# Sheet.net
KiCad netlist of a schematic drawn in Altium Designer
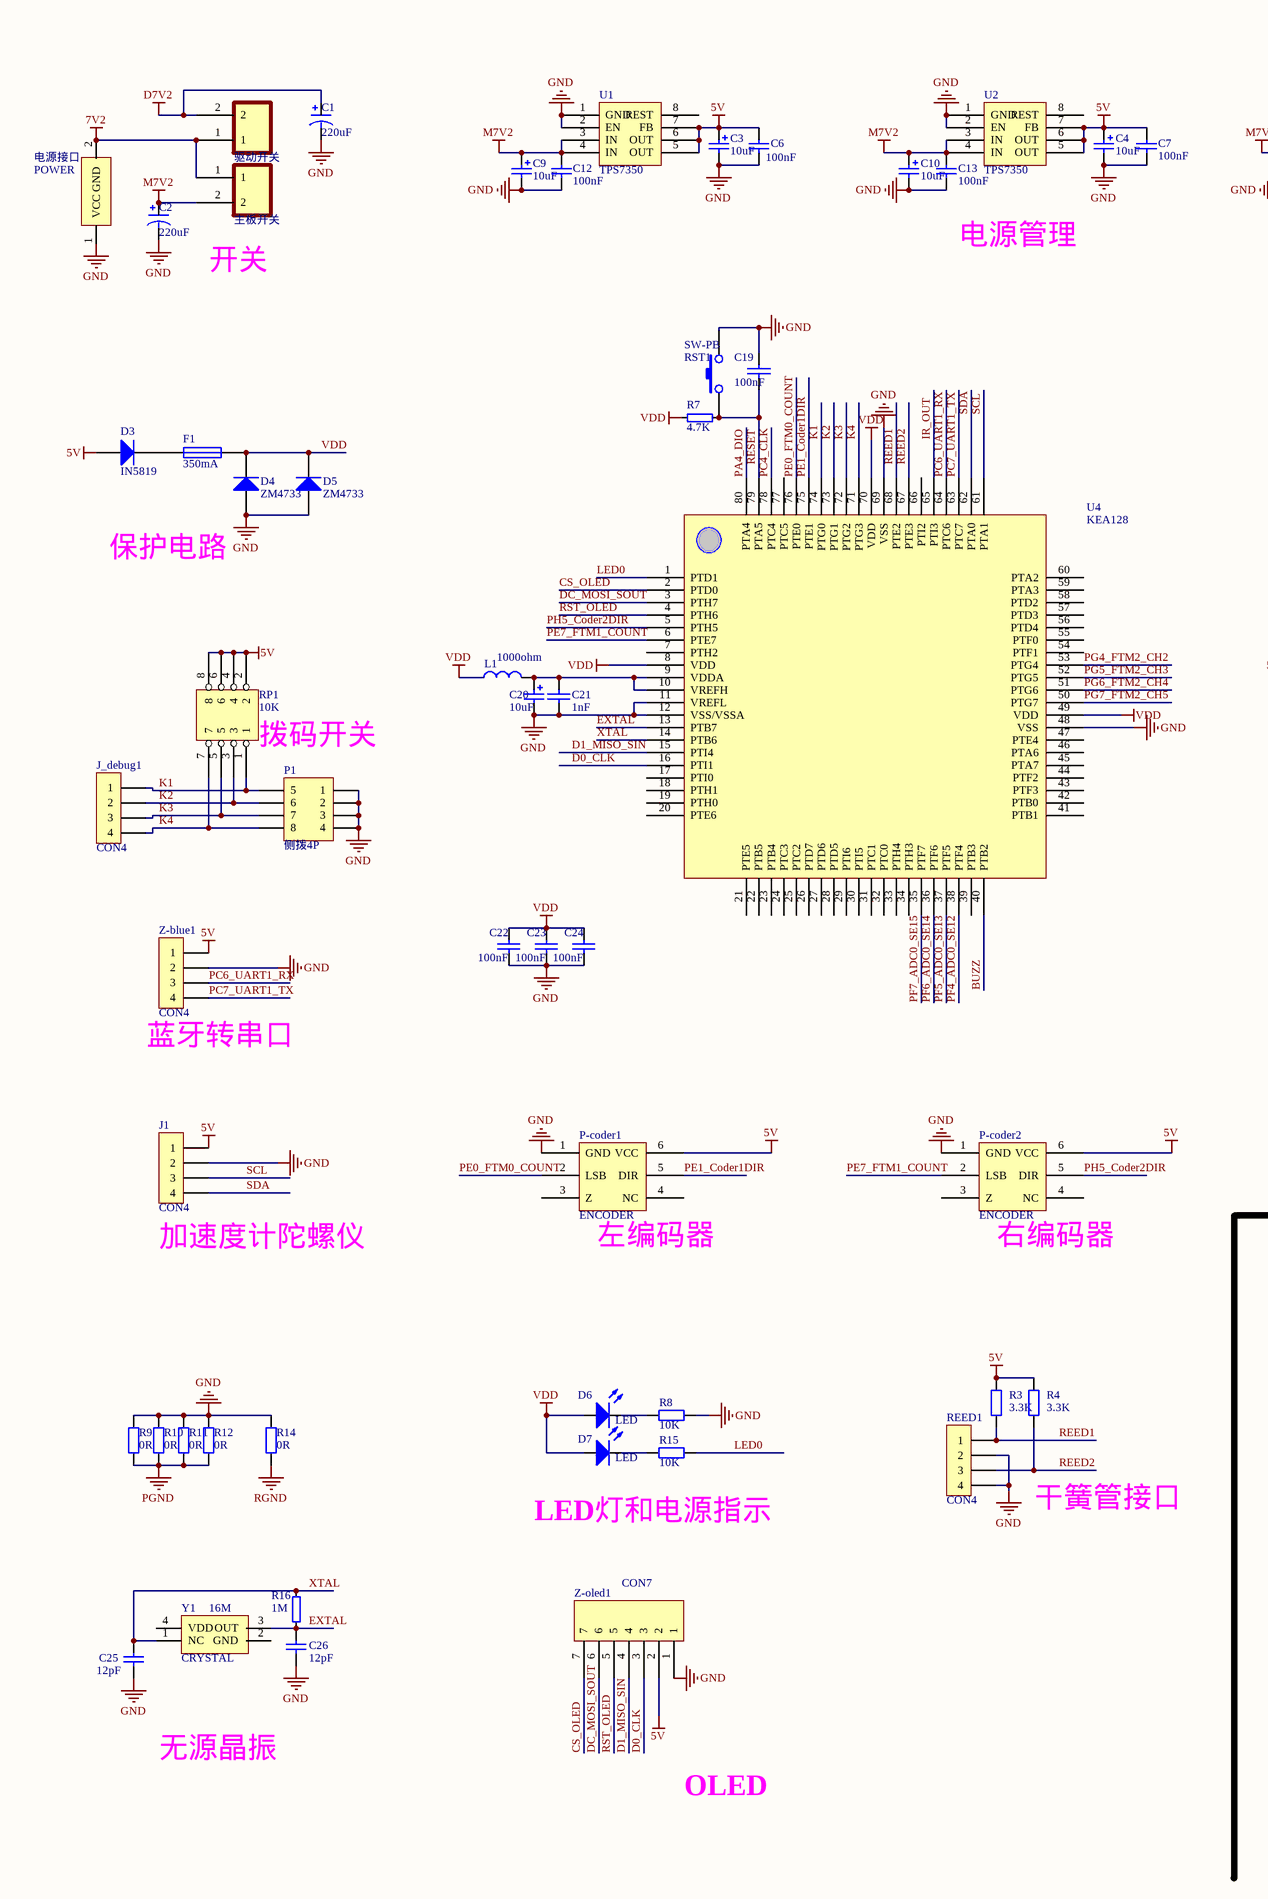
[diagram p0: 第十三届电磁Sheet.SchDoc, left]
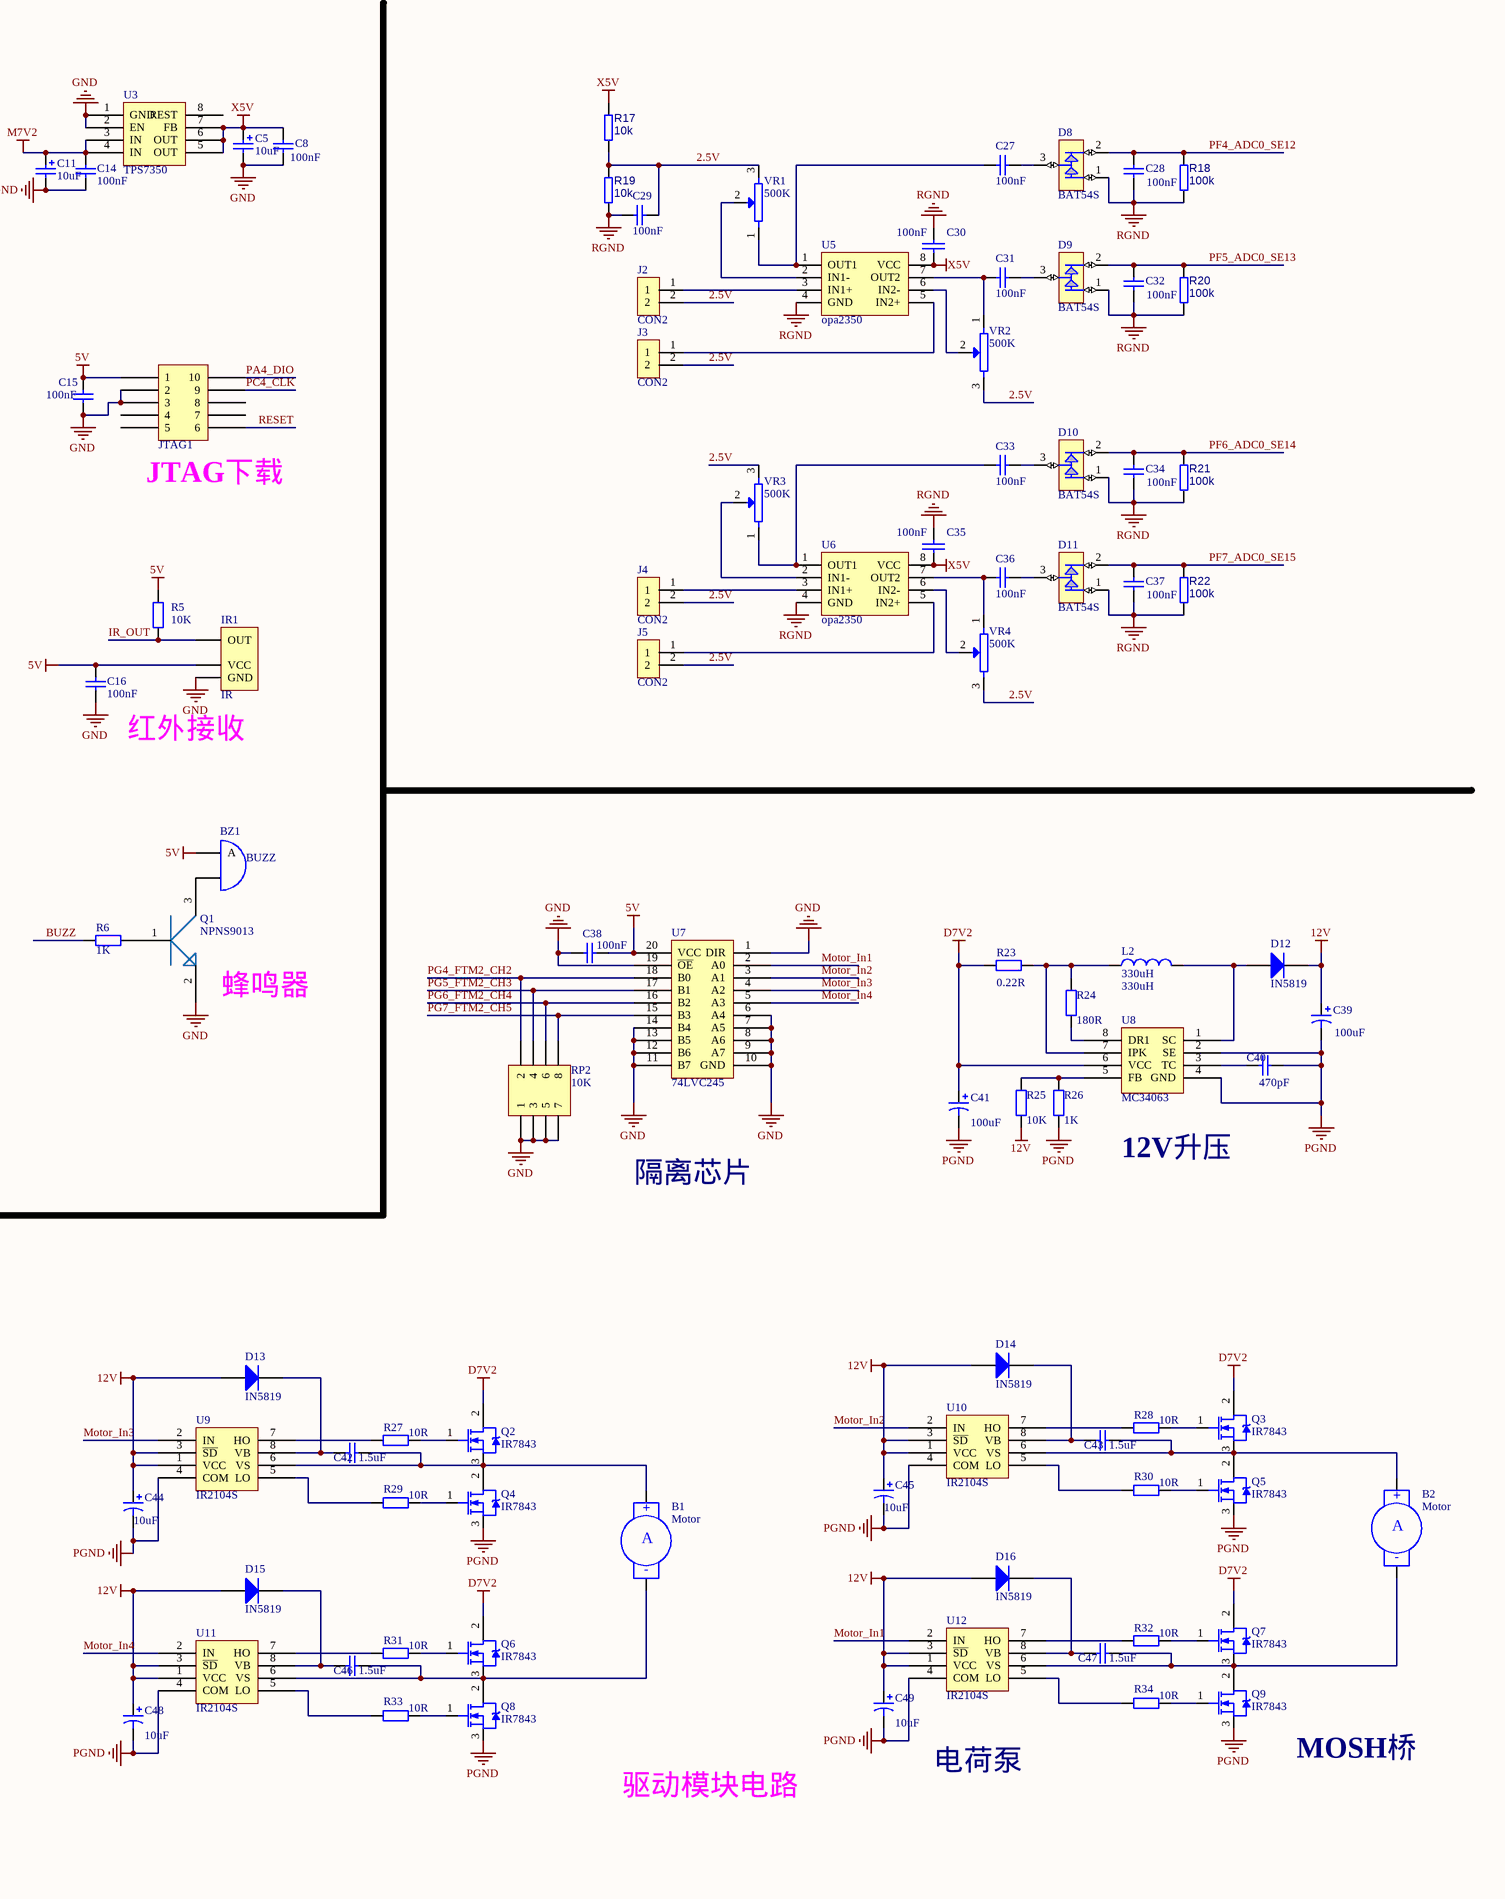
[diagram p1: 第十三届电磁Sheet.SchDoc, right]

(export (version "E")
  (design (tool "Eeschema 10.0.6"))
  (components
    (comp (ref "B1")
      (value "Motor")
      (footprint "KF301-2P")
      (description "Servo Motor")
      (libsource (lib "MOS motor driving module ") (part "Motor Servo"))
    )
    (comp (ref "B2")
      (value "Motor")
      (footprint "KF301-2P")
      (description "Servo Motor")
      (libsource (lib "MOS motor driving module ") (part "Motor Servo"))
    )
    (comp (ref "BZ1") (value "BUZZ") (footprint "BUZZ") (libsource (lib "原理图库") (part "BUZZ")))
    (comp (ref "C1")
      (value "220uF")
      (footprint "铝电解电容10*10.2")
      (description "电容带极性")
      (libsource (lib "原理图库") (part "CAP2"))
    )
    (comp (ref "C2")
      (value "220uF")
      (footprint "铝电解电容10*10.2")
      (description "电容带极性")
      (libsource (lib "原理图库") (part "CAP2"))
    )
    (comp (ref "C3") (value "10uF") (footprint "3216") (libsource (lib "飞思卡尔") (part "电容")))
    (comp (ref "C4") (value "10uF") (footprint "3216") (libsource (lib "飞思卡尔") (part "电容")))
    (comp (ref "C5") (value "10uF") (footprint "3216") (libsource (lib "飞思卡尔") (part "电容")))
    (comp (ref "C6")
      (value "100nF")
      (footprint "0603(1608)")
      (description "Capacitor")
      (libsource (lib "最小系统板K60P144-V4.0") (part "Cap"))
    )
    (comp (ref "C7")
      (value "100nF")
      (footprint "0603(1608)")
      (description "Capacitor")
      (libsource (lib "最小系统板K60P144-V4.0") (part "Cap"))
    )
    (comp (ref "C8")
      (value "100nF")
      (footprint "0603(1608)")
      (description "Capacitor")
      (libsource (lib "最小系统板K60P144-V4.0") (part "Cap"))
    )
    (comp (ref "C9") (value "10uF") (footprint "3216") (libsource (lib "飞思卡尔") (part "电容")))
    (comp (ref "C10") (value "10uF") (footprint "3216") (libsource (lib "飞思卡尔") (part "电容")))
    (comp (ref "C11") (value "10uF") (footprint "3216") (libsource (lib "飞思卡尔") (part "电容")))
    (comp (ref "C12")
      (value "100nF")
      (footprint "0603(1608)")
      (description "Capacitor")
      (libsource (lib "最小系统板K60P144-V4.0") (part "Cap"))
    )
    (comp (ref "C13")
      (value "100nF")
      (footprint "0603(1608)")
      (description "Capacitor")
      (libsource (lib "最小系统板K60P144-V4.0") (part "Cap"))
    )
    (comp (ref "C14")
      (value "100nF")
      (footprint "0603(1608)")
      (description "Capacitor")
      (libsource (lib "最小系统板K60P144-V4.0") (part "Cap"))
    )
    (comp (ref "C15")
      (value "100nF")
      (footprint "0603(1608)")
      (description "Capacitor")
      (libsource (lib "最小系统板K60P144-V4.0") (part "Cap"))
    )
    (comp (ref "C16")
      (value "100nF")
      (footprint "0603(1608)")
      (description "Capacitor")
      (fields (field (name "PUBLISHER") "Altium Limited"))
      (libsource (lib "国特原理图库") (part "Cap_1"))
    )
    (comp (ref "C19")
      (value "100nF")
      (footprint "0603(1608)")
      (description "Capacitor")
      (libsource (lib "K60芯片") (part "普通电容"))
    )
    (comp (ref "C20") (value "10uF") (footprint "3216") (libsource (lib "飞思卡尔") (part "电容")))
    (comp (ref "C21")
      (value "1nF")
      (footprint "0603(1608)")
      (description "Capacitor")
      (libsource (lib "K60芯片") (part "普通电容"))
    )
    (comp (ref "C22")
      (value "100nF")
      (footprint "0603(1608)")
      (description "Capacitor")
      (libsource (lib "K60芯片") (part "普通电容"))
    )
    (comp (ref "C23")
      (value "100nF")
      (footprint "0603(1608)")
      (description "Capacitor")
      (libsource (lib "K60芯片") (part "普通电容"))
    )
    (comp (ref "C24")
      (value "100nF")
      (footprint "0603(1608)")
      (description "Capacitor")
      (libsource (lib "K60芯片") (part "普通电容"))
    )
    (comp (ref "C25")
      (value "12pF")
      (footprint "0603(1608)")
      (description "Capacitor")
      (fields (field (name "PUBLISHER") "Altium Limited"))
      (libsource (lib "国特原理图库") (part "Cap_1"))
    )
    (comp (ref "C26")
      (value "12pF")
      (footprint "0603(1608)")
      (description "Capacitor")
      (fields (field (name "PUBLISHER") "Altium Limited"))
      (libsource (lib "国特原理图库") (part "Cap_1"))
    )
    (comp (ref "C27")
      (value "100nF")
      (footprint "0603(1608)")
      (description "Capacitor (Semiconductor SIM Model)")
      (fields (field (name "PUBLISHER") "Altium Limited"))
      (libsource (lib "电磁传感器V20") (part "Cap Semi"))
    )
    (comp (ref "C28")
      (value "100nF")
      (footprint "0603(1608)")
      (description "Capacitor (Semiconductor SIM Model)")
      (fields (field (name "PUBLISHER") "Altium Limited"))
      (libsource (lib "电磁传感器V20") (part "Cap Semi"))
    )
    (comp (ref "C29")
      (value "100nF")
      (footprint "0603(1608)")
      (description "Capacitor (Semiconductor SIM Model)")
      (fields (field (name "PUBLISHER") "Altium Limited"))
      (libsource (lib "电磁传感器V20") (part "Cap Semi"))
    )
    (comp (ref "C30")
      (value "100nF")
      (footprint "0603(1608)")
      (description "Capacitor")
      (libsource (lib "K60芯片") (part "普通电容"))
    )
    (comp (ref "C31")
      (value "100nF")
      (footprint "0603(1608)")
      (description "Capacitor (Semiconductor SIM Model)")
      (fields (field (name "PUBLISHER") "Altium Limited"))
      (libsource (lib "电磁传感器V20") (part "Cap Semi"))
    )
    (comp (ref "C32")
      (value "100nF")
      (footprint "0603(1608)")
      (description "Capacitor (Semiconductor SIM Model)")
      (fields (field (name "PUBLISHER") "Altium Limited"))
      (libsource (lib "电磁传感器V20") (part "Cap Semi"))
    )
    (comp (ref "C33")
      (value "100nF")
      (footprint "0603(1608)")
      (description "Capacitor (Semiconductor SIM Model)")
      (fields (field (name "PUBLISHER") "Altium Limited"))
      (libsource (lib "电磁传感器V20") (part "Cap Semi"))
    )
    (comp (ref "C34")
      (value "100nF")
      (footprint "0603(1608)")
      (description "Capacitor (Semiconductor SIM Model)")
      (fields (field (name "PUBLISHER") "Altium Limited"))
      (libsource (lib "电磁传感器V20") (part "Cap Semi"))
    )
    (comp (ref "C35")
      (value "100nF")
      (footprint "0603(1608)")
      (description "Capacitor")
      (libsource (lib "K60芯片") (part "普通电容"))
    )
    (comp (ref "C36")
      (value "100nF")
      (footprint "0603(1608)")
      (description "Capacitor (Semiconductor SIM Model)")
      (fields (field (name "PUBLISHER") "Altium Limited"))
      (libsource (lib "电磁传感器V20") (part "Cap Semi"))
    )
    (comp (ref "C37")
      (value "100nF")
      (footprint "0603(1608)")
      (description "Capacitor (Semiconductor SIM Model)")
      (fields (field (name "PUBLISHER") "Altium Limited"))
      (libsource (lib "电磁传感器V20") (part "Cap Semi"))
    )
    (comp (ref "C38")
      (value "100nF")
      (footprint "0603(1608)")
      (description "Capacitor")
      (fields (field (name "PUBLISHER") "Altium Limited"))
      (libsource (lib "Miscellaneous Devices") (part "Cap"))
    )
    (comp (ref "C39")
      (value "100uF")
      (footprint "TAN-D7343")
      (description "Polarized Capacitor (Radial)")
      (fields (field (name "PUBLISHER") "Altium Limited"))
      (libsource (lib "Miscellaneous Devices") (part "Cap Pol1"))
    )
    (comp (ref "C40")
      (value "470pF")
      (footprint "0603(1608)")
      (description "Capacitor")
      (fields (field (name "PUBLISHER") "Altium Limited"))
      (libsource (lib "Miscellaneous Devices") (part "Cap"))
    )
    (comp (ref "C41")
      (value "100uF")
      (footprint "TAN-D7343")
      (description "Polarized Capacitor (Radial)")
      (fields (field (name "PUBLISHER") "Altium Limited"))
      (libsource (lib "Miscellaneous Devices") (part "Cap Pol1"))
    )
    (comp (ref "C42")
      (value "1.5uF")
      (footprint "0603(1608)")
      (description "Capacitor")
      (fields (field (name "PUBLISHER") "Altium Limited"))
      (libsource (lib "Miscellaneous Devices") (part "Cap"))
    )
    (comp (ref "C43")
      (value "1.5uF")
      (footprint "0603(1608)")
      (description "Capacitor")
      (fields (field (name "PUBLISHER") "Altium Limited"))
      (libsource (lib "Miscellaneous Devices") (part "Cap"))
    )
    (comp (ref "C44")
      (value "10uF")
      (footprint "Tan-A3216")
      (description "Polarized Capacitor (Radial)")
      (fields (field (name "PUBLISHER") "Altium Limited"))
      (libsource (lib "Miscellaneous Devices") (part "Cap Pol1"))
    )
    (comp (ref "C45")
      (value "10uF")
      (footprint "Tan-A3216")
      (description "Polarized Capacitor (Radial)")
      (fields (field (name "PUBLISHER") "Altium Limited"))
      (libsource (lib "Miscellaneous Devices") (part "Cap Pol1"))
    )
    (comp (ref "C46")
      (value "1.5uF")
      (footprint "0603(1608)")
      (description "Capacitor")
      (fields (field (name "PUBLISHER") "Altium Limited"))
      (libsource (lib "Miscellaneous Devices") (part "Cap"))
    )
    (comp (ref "C47")
      (value "1.5uF")
      (footprint "0603(1608)")
      (description "Capacitor")
      (fields (field (name "PUBLISHER") "Altium Limited"))
      (libsource (lib "Miscellaneous Devices") (part "Cap"))
    )
    (comp (ref "C48")
      (value "10uF")
      (footprint "Tan-A3216")
      (description "Polarized Capacitor (Radial)")
      (fields (field (name "PUBLISHER") "Altium Limited"))
      (libsource (lib "Miscellaneous Devices") (part "Cap Pol1"))
    )
    (comp (ref "C49")
      (value "10uF")
      (footprint "Tan-A3216")
      (description "Polarized Capacitor (Radial)")
      (fields (field (name "PUBLISHER") "Altium Limited"))
      (libsource (lib "Miscellaneous Devices") (part "Cap Pol1"))
    )
    (comp (ref "D3")
      (value "IN5819")
      (footprint "LC-SOD-123")
      (description "Default Diode")
      (fields (field (name "PUBLISHER") "Altium Limited"))
      (libsource (lib "主板") (part "Diode"))
    )
    (comp (ref "D4")
      (value "ZM4733")
      (footprint "稳压管")
      (description "Default Diode")
      (fields (field (name "PUBLISHER") "Altium Limited"))
      (libsource (lib "主板") (part "Diode"))
    )
    (comp (ref "D5")
      (value "ZM4733")
      (footprint "稳压管")
      (description "Default Diode")
      (fields (field (name "PUBLISHER") "Altium Limited"))
      (libsource (lib "主板") (part "Diode"))
    )
    (comp (ref "D6")
      (value "LED")
      (footprint "0603LED")
      (description "Typical INFRARED GaAs LED")
      (libsource (lib "国特原理图库") (part "LED"))
    )
    (comp (ref "D7")
      (value "LED")
      (footprint "0603LED")
      (description "Typical INFRARED GaAs LED")
      (libsource (lib "国特原理图库") (part "LED"))
    )
    (comp (ref "D8")
      (value "BAT54S")
      (footprint "SOT23")
      (description "小信号肖特基二极管,峰值反向电压30 V,0.2A")
      (libsource (lib "电磁传感器V20") (part "BAT54S"))
    )
    (comp (ref "D9")
      (value "BAT54S")
      (footprint "SOT23")
      (description "小信号肖特基二极管,峰值反向电压30 V,0.2A")
      (libsource (lib "电磁传感器V20") (part "BAT54S"))
    )
    (comp (ref "D10")
      (value "BAT54S")
      (footprint "SOT23")
      (description "小信号肖特基二极管,峰值反向电压30 V,0.2A")
      (libsource (lib "电磁传感器V20") (part "BAT54S"))
    )
    (comp (ref "D11")
      (value "BAT54S")
      (footprint "SOT23")
      (description "小信号肖特基二极管,峰值反向电压30 V,0.2A")
      (libsource (lib "电磁传感器V20") (part "BAT54S"))
    )
    (comp (ref "D12")
      (value "IN5819")
      (footprint "LC-SOD-123")
      (description "Default Diode")
      (fields (field (name "PUBLISHER") "Altium Limited"))
      (libsource (lib "主板") (part "Diode"))
    )
    (comp (ref "D13")
      (value "IN5819")
      (footprint "LC-SOD-123")
      (description "Default Diode")
      (fields (field (name "PUBLISHER") "Altium Limited"))
      (libsource (lib "主板") (part "Diode"))
    )
    (comp (ref "D14")
      (value "IN5819")
      (footprint "LC-SOD-123")
      (description "Default Diode")
      (fields (field (name "PUBLISHER") "Altium Limited"))
      (libsource (lib "主板") (part "Diode"))
    )
    (comp (ref "D15")
      (value "IN5819")
      (footprint "LC-SOD-123")
      (description "Default Diode")
      (fields (field (name "PUBLISHER") "Altium Limited"))
      (libsource (lib "主板") (part "Diode"))
    )
    (comp (ref "D16")
      (value "IN5819")
      (footprint "LC-SOD-123")
      (description "Default Diode")
      (fields (field (name "PUBLISHER") "Altium Limited"))
      (libsource (lib "主板") (part "Diode"))
    )
    (comp (ref "F1")
      (value "350mA")
      (footprint "FUSE-1206")
      (description "Fuse")
      (fields (field (name "PUBLISHER") "Altium Limited"))
      (libsource (lib "最小系统板K60P144-V4.0") (part "Fuse 1"))
    )
    (comp (ref "IR1") (value "IR") (footprint "HS0038") (libsource (lib "原理图库") (part "IR_2")))
    (comp (ref "J1") (value "CON4") (footprint "CON4-1") (libsource (lib "原理图库") (part "CON4")))
    (comp (ref "J2") (value "CON2") (footprint "CON2") (libsource (lib "原理图库") (part "CON2")))
    (comp (ref "J3") (value "CON2") (footprint "CON2") (libsource (lib "原理图库") (part "CON2")))
    (comp (ref "J4") (value "CON2") (footprint "CON2") (libsource (lib "原理图库") (part "CON2")))
    (comp (ref "J5") (value "CON2") (footprint "CON2") (libsource (lib "原理图库") (part "CON2")))
    (comp (ref "JTAG1") (value "JTAG") (footprint "IDC5X2") (libsource (lib "国特原理图库") (part "JTAG")))
    (comp (ref "J_debug1") (value "CON4") (footprint "CON4-1") (libsource (lib "原理图库") (part "CON4")))
    (comp (ref "L1") (value "1000ohm") (footprint "0805 - duplicate") (libsource (lib "K60芯片") (part "L")))
    (comp (ref "L2")
      (value "330uH")
      (footprint "贴片电感7*7*4")
      (description "Inductor")
      (fields (field (name "ALTIUM_VALUE") "330uH") (field (name "PUBLISHER") "Altium Limited"))
      (libsource (lib "Miscellaneous Devices") (part "Inductor"))
    )
    (comp (ref "P-coder1") (value "ENCODER") (footprint "ENCODER") (libsource (lib "原理图库") (part "ENCODER")))
    (comp (ref "P-coder2") (value "ENCODER") (footprint "ENCODER") (libsource (lib "原理图库") (part "ENCODER")))
    (comp (ref "P1") (value "侧拨4P") (footprint "侧拨4P") (libsource (lib "原理图库") (part "侧拨4P")))
    (comp (ref "POWER")
      (value "电源接口")
      (footprint "KF301-2P")
      (description "2P")
      (libsource (lib "原理图库") (part "电源接口"))
    )
    (comp (ref "Q1")
      (value "NPNS9013")
      (footprint "LC-SOT-23(SOT-23-3)")
      (libsource (lib "原理图库") (part "S9013"))
    )
    (comp (ref "Q2")
      (value "IR7843")
      (footprint "LR7843")
      (description "N-Channel Power MOSFET")
      (fields (field (name "PUBLISHER") "Altium Limited"))
      (libsource (lib "MOS motor driving module ") (part "NMOS-2"))
    )
    (comp (ref "Q3")
      (value "IR7843")
      (footprint "LR7843")
      (description "N-Channel Power MOSFET")
      (fields (field (name "PUBLISHER") "Altium Limited"))
      (libsource (lib "MOS motor driving module ") (part "NMOS-2"))
    )
    (comp (ref "Q4")
      (value "IR7843")
      (footprint "LR7843 - no via")
      (description "N-Channel Power MOSFET")
      (fields (field (name "PUBLISHER") "Altium Limited"))
      (libsource (lib "MOS motor driving module ") (part "NMOS-2"))
    )
    (comp (ref "Q5")
      (value "IR7843")
      (footprint "LR7843 - no via")
      (description "N-Channel Power MOSFET")
      (fields (field (name "PUBLISHER") "Altium Limited"))
      (libsource (lib "MOS motor driving module ") (part "NMOS-2"))
    )
    (comp (ref "Q6")
      (value "IR7843")
      (footprint "LR7843")
      (description "N-Channel Power MOSFET")
      (fields (field (name "PUBLISHER") "Altium Limited"))
      (libsource (lib "MOS motor driving module ") (part "NMOS-2"))
    )
    (comp (ref "Q7")
      (value "IR7843")
      (footprint "LR7843")
      (description "N-Channel Power MOSFET")
      (fields (field (name "PUBLISHER") "Altium Limited"))
      (libsource (lib "MOS motor driving module ") (part "NMOS-2"))
    )
    (comp (ref "Q8")
      (value "IR7843")
      (footprint "LR7843 - no via")
      (description "N-Channel Power MOSFET")
      (fields (field (name "PUBLISHER") "Altium Limited"))
      (libsource (lib "MOS motor driving module ") (part "NMOS-2"))
    )
    (comp (ref "Q9")
      (value "IR7843")
      (footprint "LR7843 - no via")
      (description "N-Channel Power MOSFET")
      (fields (field (name "PUBLISHER") "Altium Limited"))
      (libsource (lib "MOS motor driving module ") (part "NMOS-2"))
    )
    (comp (ref "R3")
      (value "3.3K")
      (footprint "0603(1608)")
      (description "Resistor")
      (fields (field (name "PUBLISHER") "Altium Limited"))
      (libsource (lib "国特原理图库") (part "Res2_2"))
    )
    (comp (ref "R4")
      (value "3.3K")
      (footprint "0603(1608)")
      (description "Resistor")
      (fields (field (name "PUBLISHER") "Altium Limited"))
      (libsource (lib "国特原理图库") (part "Res2_2"))
    )
    (comp (ref "R5")
      (value "10K")
      (footprint "0603(1608)")
      (description "Resistor")
      (fields (field (name "PUBLISHER") "Altium Limited"))
      (libsource (lib "国特原理图库") (part "Res2_2"))
    )
    (comp (ref "R6")
      (value "1K")
      (footprint "0603(1608)")
      (description "Resistor")
      (fields (field (name "PUBLISHER") "Altium Limited"))
      (libsource (lib "") (part "Res2_2_1"))
    )
    (comp (ref "R7") (value "4.7K") (footprint "0603(1608)") (libsource (lib "K60芯片") (part "RES")))
    (comp (ref "R8")
      (value "10K")
      (footprint "0603(1608)")
      (description "Resistor")
      (fields (field (name "PUBLISHER") "Altium Limited"))
      (libsource (lib "国特原理图库") (part "Res2_1"))
    )
    (comp (ref "R9") (value "0R") (footprint "0805(2012)") (libsource (lib "飞思卡尔") (part "RES")))
    (comp (ref "R10") (value "0R") (footprint "0805(2012)") (libsource (lib "飞思卡尔") (part "RES")))
    (comp (ref "R11") (value "0R") (footprint "0805(2012)") (libsource (lib "飞思卡尔") (part "RES")))
    (comp (ref "R12") (value "0R") (footprint "0805(2012)") (libsource (lib "飞思卡尔") (part "RES")))
    (comp (ref "R14") (value "0R") (footprint "0805(2012)") (libsource (lib "飞思卡尔") (part "RES")))
    (comp (ref "R15")
      (value "10K")
      (footprint "0603(1608)")
      (description "Resistor")
      (fields (field (name "PUBLISHER") "Altium Limited"))
      (libsource (lib "国特原理图库") (part "Res2_1"))
    )
    (comp (ref "R16") (value "1M") (footprint "0603(1608)") (libsource (lib "K60芯片") (part "RES")))
    (comp (ref "R17")
      (value "10k")
      (footprint "0603(1608)")
      (description "单个电阻")
      (fields (field (name "PUBLISHER") "Altium Limited"))
      (libsource (lib "电磁传感器V20") (part "RES"))
    )
    (comp (ref "R18")
      (value "100k")
      (footprint "0603(1608)")
      (description "单个电阻")
      (fields (field (name "PUBLISHER") "Altium Limited"))
      (libsource (lib "电磁传感器V20") (part "RES"))
    )
    (comp (ref "R19")
      (value "10k")
      (footprint "0603(1608)")
      (description "单个电阻")
      (fields (field (name "PUBLISHER") "Altium Limited"))
      (libsource (lib "电磁传感器V20") (part "RES"))
    )
    (comp (ref "R20")
      (value "100k")
      (footprint "0603(1608)")
      (description "单个电阻")
      (fields (field (name "PUBLISHER") "Altium Limited"))
      (libsource (lib "电磁传感器V20") (part "RES"))
    )
    (comp (ref "R21")
      (value "100k")
      (footprint "0603(1608)")
      (description "单个电阻")
      (fields (field (name "PUBLISHER") "Altium Limited"))
      (libsource (lib "电磁传感器V20") (part "RES"))
    )
    (comp (ref "R22")
      (value "100k")
      (footprint "0603(1608)")
      (description "单个电阻")
      (fields (field (name "PUBLISHER") "Altium Limited"))
      (libsource (lib "电磁传感器V20") (part "RES"))
    )
    (comp (ref "R23")
      (value "0.22R")
      (footprint "0603(1608)")
      (description "Resistor")
      (fields (field (name "PUBLISHER") "Altium Limited"))
      (libsource (lib "Miscellaneous Devices") (part "Res2"))
    )
    (comp (ref "R24")
      (value "180R")
      (footprint "0603(1608)")
      (description "Resistor")
      (fields (field (name "PUBLISHER") "Altium Limited"))
      (libsource (lib "") (part "Res2_1"))
    )
    (comp (ref "R25")
      (value "10K")
      (footprint "0603(1608)")
      (description "Resistor")
      (fields (field (name "PUBLISHER") "Altium Limited"))
      (libsource (lib "") (part "Res2_1"))
    )
    (comp (ref "R26")
      (value "1K")
      (footprint "0603(1608)")
      (description "Resistor")
      (fields (field (name "PUBLISHER") "Altium Limited"))
      (libsource (lib "") (part "Res2_1"))
    )
    (comp (ref "R27")
      (value "10R")
      (footprint "0603(1608)")
      (description "Resistor")
      (fields (field (name "PUBLISHER") "Altium Limited"))
      (libsource (lib "MOS motor driving module ") (part "Res2"))
    )
    (comp (ref "R28")
      (value "10R")
      (footprint "0603(1608)")
      (description "Resistor")
      (fields (field (name "PUBLISHER") "Altium Limited"))
      (libsource (lib "MOS motor driving module ") (part "Res2"))
    )
    (comp (ref "R29")
      (value "10R")
      (footprint "0603(1608)")
      (description "Resistor")
      (fields (field (name "PUBLISHER") "Altium Limited"))
      (libsource (lib "MOS motor driving module ") (part "Res2"))
    )
    (comp (ref "R30")
      (value "10R")
      (footprint "0603(1608)")
      (description "Resistor")
      (fields (field (name "PUBLISHER") "Altium Limited"))
      (libsource (lib "MOS motor driving module ") (part "Res2"))
    )
    (comp (ref "R31")
      (value "10R")
      (footprint "0603(1608)")
      (description "Resistor")
      (fields (field (name "PUBLISHER") "Altium Limited"))
      (libsource (lib "MOS motor driving module ") (part "Res2"))
    )
    (comp (ref "R32")
      (value "10R")
      (footprint "0603(1608)")
      (description "Resistor")
      (fields (field (name "PUBLISHER") "Altium Limited"))
      (libsource (lib "MOS motor driving module ") (part "Res2"))
    )
    (comp (ref "R33")
      (value "10R")
      (footprint "0603(1608)")
      (description "Resistor")
      (fields (field (name "PUBLISHER") "Altium Limited"))
      (libsource (lib "MOS motor driving module ") (part "Res2"))
    )
    (comp (ref "R34")
      (value "10R")
      (footprint "0603(1608)")
      (description "Resistor")
      (fields (field (name "PUBLISHER") "Altium Limited"))
      (libsource (lib "MOS motor driving module ") (part "Res2"))
    )
    (comp (ref "REED1") (value "CON4") (footprint "CON4-1") (libsource (lib "主板") (part "CON4")))
    (comp (ref "RP1") (value "10K") (footprint "RA_8") (libsource (lib "原理图库") (part "HEADER4*2")))
    (comp (ref "RP2")
      (value "10K")
      (footprint "RA_8")
      (description "Header, 4-Pin, Dual row")
      (fields (field (name "PUBLISHER") "Altium Limited"))
      (libsource (lib "Miscellaneous Connectors") (part "Header 4X2"))
    )
    (comp (ref "RST1") (value "SW-PB") (footprint "SMT_BUTTON") (libsource (lib "K60芯片") (part "微动开关")))
    (comp (ref "U1") (value "TPS7350") (footprint "SOIC-8") (libsource (lib "飞思卡尔") (part "TPS")))
    (comp (ref "U2") (value "TPS7350") (footprint "SOIC-8") (libsource (lib "飞思卡尔") (part "TPS")))
    (comp (ref "U3") (value "TPS7350") (footprint "SOIC-8") (libsource (lib "飞思卡尔") (part "TPS")))
    (comp (ref "U4") (value "KEA128") (footprint "LQFP-80M") (libsource (lib "主板") (part "KEA128-80")))
    (comp (ref "U5")
      (value "opa2350")
      (footprint "SO8")
      (description "放大器")
      (libsource (lib "opa2350") (part "opa2350"))
    )
    (comp (ref "U6")
      (value "opa2350")
      (footprint "SO8")
      (description "放大器")
      (libsource (lib "opa2350") (part "opa2350"))
    )
    (comp (ref "U7")
      (value "74LVC245")
      (footprint "74LVC245 TSSOP")
      (libsource (lib "原理图库") (part "74LVC245"))
    )
    (comp (ref "U8") (value "MC34063") (footprint "MC34063") (libsource (lib "原理图库") (part "MC34063")))
    (comp (ref "U9")
      (value "IR2104S")
      (footprint "IR2104")
      (libsource (lib "MOS motor driving module ") (part "IR2104S"))
    )
    (comp (ref "U10")
      (value "IR2104S")
      (footprint "IR2104")
      (libsource (lib "MOS motor driving module ") (part "IR2104S"))
    )
    (comp (ref "U11")
      (value "IR2104S")
      (footprint "IR2104")
      (libsource (lib "MOS motor driving module ") (part "IR2104S"))
    )
    (comp (ref "U12")
      (value "IR2104S")
      (footprint "IR2104")
      (libsource (lib "MOS motor driving module ") (part "IR2104S"))
    )
    (comp (ref "VR1")
      (value "500K")
      (footprint "电位器")
      (description "3端可调电阻")
      (libsource (lib "电磁传感器V20") (part "VR"))
    )
    (comp (ref "VR2")
      (value "500K")
      (footprint "电位器")
      (description "3端可调电阻")
      (libsource (lib "电磁传感器V20") (part "VR"))
    )
    (comp (ref "VR3")
      (value "500K")
      (footprint "电位器")
      (description "3端可调电阻")
      (libsource (lib "电磁传感器V20") (part "VR"))
    )
    (comp (ref "VR4")
      (value "500K")
      (footprint "电位器")
      (description "3端可调电阻")
      (libsource (lib "电磁传感器V20") (part "VR"))
    )
    (comp (ref "Y1")
      (value "CRYSTAL")
      (footprint "LC-SMD-3225_4P")
      (fields (field (name "ALTIUM_UNNAMED_1") "16M"))
      (libsource (lib "原理图库") (part "CRYSTAL"))
    )
    (comp (ref "Z-blue1") (value "CON4") (footprint "Bluetooth") (libsource (lib "原理图库") (part "CON4")))
    (comp (ref "Z-oled1") (value "CON7") (footprint "CON7_OLED") (libsource (lib "原理图库") (part "CON7")))
    (comp (ref "主板开关1") (value "主板开关") (footprint "船型开关-small") (libsource (lib "国特原理图库") (part "船型开关")))
    (comp (ref "驱动开关1") (value "驱动开关") (footprint "船型开关-small") (libsource (lib "") (part "船型开关_1")))
  )
  (nets
    (net (code "1") (name "/2.5V") (class "Default")
      (node (ref "C29") (pin "1") (pinfunction "1_1") (pintype "passive"))
      (node (ref "J2") (pin "2") (pinfunction "2_2") (pintype "passive"))
      (node (ref "J3") (pin "2") (pinfunction "2_2") (pintype "passive"))
      (node (ref "J4") (pin "2") (pinfunction "2_2") (pintype "passive"))
      (node (ref "J5") (pin "2") (pinfunction "2_2") (pintype "passive"))
      (node (ref "R17") (pin "1") (pinfunction "1_1") (pintype "passive"))
      (node (ref "R19") (pin "2") (pinfunction "2_2") (pintype "passive"))
      (node (ref "VR1") (pin "3") (pinfunction "3_3") (pintype "passive"))
      (node (ref "VR2") (pin "3") (pinfunction "3_3") (pintype "passive"))
      (node (ref "VR3") (pin "3") (pinfunction "3_3") (pintype "passive"))
      (node (ref "VR4") (pin "3") (pinfunction "3_3") (pintype "passive"))
    )
    (net (code "2") (name "/BUZZ") (class "Default")
      (node (ref "R6") (pin "2") (pinfunction "2_2") (pintype "passive"))
      (node (ref "U4") (pin "40") (pinfunction "PTB2_40") (pintype "passive"))
    )
    (net (code "3") (name "/CS_OLED") (class "Default")
      (node (ref "U4") (pin "2") (pinfunction "PTD0_2") (pintype "passive"))
      (node (ref "Z-oled1") (pin "7") (pinfunction "7_7") (pintype "passive"))
    )
    (net (code "4") (name "/D0_CLK") (class "Default")
      (node (ref "U4") (pin "16") (pinfunction "PTI1_16") (pintype "passive"))
      (node (ref "Z-oled1") (pin "3") (pinfunction "3_3") (pintype "passive"))
    )
    (net (code "5") (name "/D1_MISO_SIN") (class "Default")
      (node (ref "U4") (pin "15") (pinfunction "PTI4_15") (pintype "passive"))
      (node (ref "Z-oled1") (pin "4") (pinfunction "4_4") (pintype "passive"))
    )
    (net (code "6") (name "/DC_MOSI_SOUT") (class "Default")
      (node (ref "U4") (pin "3") (pinfunction "PTH7_3") (pintype "passive"))
      (node (ref "Z-oled1") (pin "6") (pinfunction "6_6") (pintype "passive"))
    )
    (net (code "7") (name "/EXTAL") (class "Default")
      (node (ref "C26") (pin "2") (pinfunction "2_2") (pintype "passive"))
      (node (ref "R16") (pin "2") (pinfunction "2_2") (pintype "passive"))
      (node (ref "U4") (pin "13") (pinfunction "PTB7_13") (pintype "passive"))
      (node (ref "Y1") (pin "3") (pinfunction "OUT_3") (pintype "passive"))
    )
    (net (code "8") (name "/IR_OUT") (class "Default")
      (node (ref "IR1") (pin "3") (pinfunction "OUT_3") (pintype "passive"))
      (node (ref "R5") (pin "1") (pinfunction "1_1") (pintype "passive"))
      (node (ref "U4") (pin "65") (pinfunction "PTI3_65") (pintype "passive"))
    )
    (net (code "9") (name "/K1") (class "Default")
      (node (ref "J_debug1") (pin "1") (pinfunction "1_1") (pintype "passive"))
      (node (ref "P1") (pin "5") (pinfunction "5_5") (pintype "passive"))
      (node (ref "RP1") (pin "1") (pinfunction "1_1") (pintype "passive"))
      (node (ref "U4") (pin "74") (pinfunction "PTG0_74") (pintype "passive"))
    )
    (net (code "10") (name "/K2") (class "Default")
      (node (ref "J_debug1") (pin "2") (pinfunction "2_2") (pintype "passive"))
      (node (ref "P1") (pin "6") (pinfunction "6_6") (pintype "passive"))
      (node (ref "RP1") (pin "3") (pinfunction "3_3") (pintype "passive"))
      (node (ref "U4") (pin "73") (pinfunction "PTG1_73") (pintype "passive"))
    )
    (net (code "11") (name "/K3") (class "Default")
      (node (ref "J_debug1") (pin "3") (pinfunction "3_3") (pintype "passive"))
      (node (ref "P1") (pin "7") (pinfunction "7_7") (pintype "passive"))
      (node (ref "RP1") (pin "5") (pinfunction "5_5") (pintype "passive"))
      (node (ref "U4") (pin "72") (pinfunction "PTG2_72") (pintype "passive"))
    )
    (net (code "12") (name "/K4") (class "Default")
      (node (ref "J_debug1") (pin "4") (pinfunction "4_4") (pintype "passive"))
      (node (ref "P1") (pin "8") (pinfunction "8_8") (pintype "passive"))
      (node (ref "RP1") (pin "7") (pinfunction "7_7") (pintype "passive"))
      (node (ref "U4") (pin "71") (pinfunction "PTG3_71") (pintype "passive"))
    )
    (net (code "13") (name "/LED0") (class "Default")
      (node (ref "R15") (pin "2") (pinfunction "2_2") (pintype "passive"))
      (node (ref "U4") (pin "1") (pinfunction "PTD1_1") (pintype "passive"))
    )
    (net (code "14") (name "/Motor_In1") (class "Default")
      (node (ref "U12") (pin "2") (pinfunction "IN_2") (pintype "passive"))
      (node (ref "U7") (pin "2") (pinfunction "A0_2") (pintype "passive"))
    )
    (net (code "15") (name "/Motor_In2") (class "Default")
      (node (ref "U10") (pin "2") (pinfunction "IN_2") (pintype "passive"))
      (node (ref "U7") (pin "3") (pinfunction "A1_3") (pintype "passive"))
    )
    (net (code "16") (name "/Motor_In3") (class "Default")
      (node (ref "U7") (pin "4") (pinfunction "A2_4") (pintype "passive"))
      (node (ref "U9") (pin "2") (pinfunction "IN_2") (pintype "passive"))
    )
    (net (code "17") (name "/Motor_In4") (class "Default")
      (node (ref "U11") (pin "2") (pinfunction "IN_2") (pintype "passive"))
      (node (ref "U7") (pin "5") (pinfunction "A3_5") (pintype "passive"))
    )
    (net (code "18") (name "/PA4_DIO") (class "Default")
      (node (ref "JTAG1") (pin "10") (pinfunction "10_10") (pintype "passive"))
      (node (ref "U4") (pin "80") (pinfunction "PTA4_80") (pintype "passive"))
    )
    (net (code "19") (name "/PC4_CLK") (class "Default")
      (node (ref "JTAG1") (pin "9") (pinfunction "9_9") (pintype "passive"))
      (node (ref "U4") (pin "78") (pinfunction "PTC4_78") (pintype "passive"))
    )
    (net (code "20") (name "/PC6_UART1_RX") (class "Default")
      (node (ref "U4") (pin "64") (pinfunction "PTC6_64") (pintype "passive"))
      (node (ref "Z-blue1") (pin "3") (pinfunction "3_3") (pintype "passive"))
    )
    (net (code "21") (name "/PC7_UART1_TX") (class "Default")
      (node (ref "U4") (pin "63") (pinfunction "PTC7_63") (pintype "passive"))
      (node (ref "Z-blue1") (pin "4") (pinfunction "4_4") (pintype "passive"))
    )
    (net (code "22") (name "/PE0_FTM0_COUNT") (class "Default")
      (node (ref "P-coder1") (pin "2") (pinfunction "LSB_2") (pintype "passive"))
      (node (ref "U4") (pin "76") (pinfunction "PTE0_76") (pintype "passive"))
    )
    (net (code "23") (name "/PE1_Coder1DIR") (class "Default")
      (node (ref "P-coder1") (pin "5") (pinfunction "DIR_5") (pintype "passive"))
      (node (ref "U4") (pin "75") (pinfunction "PTE1_75") (pintype "passive"))
    )
    (net (code "24") (name "/PE7_FTM1_COUNT") (class "Default")
      (node (ref "P-coder2") (pin "2") (pinfunction "LSB_2") (pintype "passive"))
      (node (ref "U4") (pin "6") (pinfunction "PTE7_6") (pintype "passive"))
    )
    (net (code "25") (name "/PF4_ADC0_SE12") (class "Default")
      (node (ref "C28") (pin "2") (pinfunction "2_2") (pintype "passive"))
      (node (ref "D8") (pin "2") (pintype "bidirectional"))
      (node (ref "R18") (pin "2") (pinfunction "2_2") (pintype "passive"))
      (node (ref "U4") (pin "38") (pinfunction "PTF4_38") (pintype "passive"))
    )
    (net (code "26") (name "/PF5_ADC0_SE13") (class "Default")
      (node (ref "C32") (pin "2") (pinfunction "2_2") (pintype "passive"))
      (node (ref "D9") (pin "2") (pintype "bidirectional"))
      (node (ref "R20") (pin "2") (pinfunction "2_2") (pintype "passive"))
      (node (ref "U4") (pin "37") (pinfunction "PTF5_37") (pintype "passive"))
    )
    (net (code "27") (name "/PF6_ADC0_SE14") (class "Default")
      (node (ref "C34") (pin "2") (pinfunction "2_2") (pintype "passive"))
      (node (ref "D10") (pin "2") (pintype "bidirectional"))
      (node (ref "R21") (pin "2") (pinfunction "2_2") (pintype "passive"))
      (node (ref "U4") (pin "36") (pinfunction "PTF6_36") (pintype "passive"))
    )
    (net (code "28") (name "/PF7_ADC0_SE15") (class "Default")
      (node (ref "C37") (pin "2") (pinfunction "2_2") (pintype "passive"))
      (node (ref "D11") (pin "2") (pintype "bidirectional"))
      (node (ref "R22") (pin "2") (pinfunction "2_2") (pintype "passive"))
      (node (ref "U4") (pin "35") (pinfunction "PTF7_35") (pintype "passive"))
    )
    (net (code "29") (name "/PG4_FTM2_CH2") (class "Default")
      (node (ref "RP2") (pin "2") (pinfunction "2_2") (pintype "passive"))
      (node (ref "U4") (pin "53") (pinfunction "PTG4_53") (pintype "passive"))
      (node (ref "U7") (pin "18") (pinfunction "B0_18") (pintype "passive"))
    )
    (net (code "30") (name "/PG5_FTM2_CH3") (class "Default")
      (node (ref "RP2") (pin "4") (pinfunction "4_4") (pintype "passive"))
      (node (ref "U4") (pin "52") (pinfunction "PTG5_52") (pintype "passive"))
      (node (ref "U7") (pin "17") (pinfunction "B1_17") (pintype "passive"))
    )
    (net (code "31") (name "/PG6_FTM2_CH4") (class "Default")
      (node (ref "RP2") (pin "6") (pinfunction "6_6") (pintype "passive"))
      (node (ref "U4") (pin "51") (pinfunction "PTG6_51") (pintype "passive"))
      (node (ref "U7") (pin "16") (pinfunction "B2_16") (pintype "passive"))
    )
    (net (code "32") (name "/PG7_FTM2_CH5") (class "Default")
      (node (ref "RP2") (pin "8") (pinfunction "8_8") (pintype "passive"))
      (node (ref "U4") (pin "50") (pinfunction "PTG7_50") (pintype "passive"))
      (node (ref "U7") (pin "15") (pinfunction "B3_15") (pintype "passive"))
    )
    (net (code "33") (name "/PH5_Coder2DIR") (class "Default")
      (node (ref "P-coder2") (pin "5") (pinfunction "DIR_5") (pintype "passive"))
      (node (ref "U4") (pin "5") (pinfunction "PTH5_5") (pintype "passive"))
    )
    (net (code "34") (name "/REED1") (class "Default")
      (node (ref "R3") (pin "1") (pinfunction "1_1") (pintype "passive"))
      (node (ref "REED1") (pin "1") (pinfunction "1_1") (pintype "passive"))
      (node (ref "U4") (pin "68") (pinfunction "PTE2_68") (pintype "passive"))
    )
    (net (code "35") (name "/REED2") (class "Default")
      (node (ref "R4") (pin "1") (pinfunction "1_1") (pintype "passive"))
      (node (ref "REED1") (pin "3") (pinfunction "3_3") (pintype "passive"))
      (node (ref "U4") (pin "67") (pinfunction "PTE3_67") (pintype "passive"))
    )
    (net (code "36") (name "/RESET") (class "Default")
      (node (ref "C19") (pin "1") (pinfunction "1_1") (pintype "passive"))
      (node (ref "JTAG1") (pin "6") (pinfunction "6_6") (pintype "passive"))
      (node (ref "R7") (pin "2") (pinfunction "2_2") (pintype "passive"))
      (node (ref "RST1") (pin "1") (pinfunction "1_1") (pintype "passive"))
      (node (ref "U4") (pin "79") (pinfunction "PTA5_79") (pintype "passive"))
    )
    (net (code "37") (name "/RST_OLED") (class "Default")
      (node (ref "U4") (pin "4") (pinfunction "PTH6_4") (pintype "passive"))
      (node (ref "Z-oled1") (pin "5") (pinfunction "5_5") (pintype "passive"))
    )
    (net (code "38") (name "/SCL") (class "Default")
      (node (ref "J1") (pin "3") (pinfunction "3_3") (pintype "passive"))
      (node (ref "U4") (pin "61") (pinfunction "PTA1_61") (pintype "passive"))
    )
    (net (code "39") (name "/SDA") (class "Default")
      (node (ref "J1") (pin "4") (pinfunction "4_4") (pintype "passive"))
      (node (ref "U4") (pin "62") (pinfunction "PTA0_62") (pintype "passive"))
    )
    (net (code "40") (name "/XTAL") (class "Default")
      (node (ref "C25") (pin "2") (pinfunction "2_2") (pintype "passive"))
      (node (ref "R16") (pin "1") (pinfunction "1_1") (pintype "passive"))
      (node (ref "U4") (pin "14") (pinfunction "PTB6_14") (pintype "passive"))
      (node (ref "Y1") (pin "1") (pinfunction "NC_1") (pintype "passive"))
    )
    (net (code "41") (name "5V") (class "Default")
      (node (ref "BZ1") (pin "1") (pinfunction "A_1") (pintype "passive"))
      (node (ref "C15") (pin "2") (pinfunction "2_2") (pintype "passive"))
      (node (ref "C16") (pin "2") (pinfunction "2_2") (pintype "passive"))
      (node (ref "C3") (pin "1") (pinfunction "1_1") (pintype "passive"))
      (node (ref "C38") (pin "2") (pinfunction "2_2") (pintype "passive"))
      (node (ref "C4") (pin "1") (pinfunction "1_1") (pintype "passive"))
      (node (ref "C6") (pin "2") (pinfunction "2_2") (pintype "passive"))
      (node (ref "C7") (pin "2") (pinfunction "2_2") (pintype "passive"))
      (node (ref "D3") (pin "1") (pinfunction "A_1") (pintype "passive"))
      (node (ref "IR1") (pin "2") (pinfunction "VCC_2") (pintype "passive"))
      (node (ref "J1") (pin "1") (pinfunction "1_1") (pintype "passive"))
      (node (ref "JTAG1") (pin "1") (pinfunction "1_1") (pintype "passive"))
      (node (ref "P-coder1") (pin "6") (pinfunction "VCC_6") (pintype "passive"))
      (node (ref "P-coder2") (pin "6") (pinfunction "VCC_6") (pintype "passive"))
      (node (ref "R3") (pin "2") (pinfunction "2_2") (pintype "passive"))
      (node (ref "R4") (pin "2") (pinfunction "2_2") (pintype "passive"))
      (node (ref "R5") (pin "2") (pinfunction "2_2") (pintype "passive"))
      (node (ref "RP1") (pin "2") (pinfunction "2_2") (pintype "passive"))
      (node (ref "RP1") (pin "4") (pinfunction "4_4") (pintype "passive"))
      (node (ref "RP1") (pin "6") (pinfunction "6_6") (pintype "passive"))
      (node (ref "RP1") (pin "8") (pinfunction "8_8") (pintype "passive"))
      (node (ref "U1") (pin "5") (pinfunction "OUT_5") (pintype "passive"))
      (node (ref "U1") (pin "6") (pinfunction "OUT_6") (pintype "passive"))
      (node (ref "U1") (pin "7") (pinfunction "FB_7") (pintype "passive"))
      (node (ref "U2") (pin "5") (pinfunction "OUT_5") (pintype "passive"))
      (node (ref "U2") (pin "6") (pinfunction "OUT_6") (pintype "passive"))
      (node (ref "U2") (pin "7") (pinfunction "FB_7") (pintype "passive"))
      (node (ref "U7") (pin "20") (pinfunction "VCC_20") (pintype "passive"))
      (node (ref "Z-blue1") (pin "1") (pinfunction "1_1") (pintype "passive"))
      (node (ref "Z-oled1") (pin "2") (pinfunction "2_2") (pintype "passive"))
    )
    (net (code "42") (name "7V2") (class "Default")
      (node (ref "POWER") (pin "2") (pinfunction "GND_2") (pintype "passive"))
      (node (ref "主板开关1") (pin "1") (pinfunction "1_1") (pintype "passive"))
      (node (ref "驱动开关1") (pin "1") (pinfunction "1_1") (pintype "passive"))
    )
    (net (code "43") (name "12V") (class "Default")
      (node (ref "C39") (pin "1") (pinfunction "1_1") (pintype "passive"))
      (node (ref "C44") (pin "1") (pinfunction "1_1") (pintype "passive"))
      (node (ref "C45") (pin "1") (pinfunction "1_1") (pintype "passive"))
      (node (ref "C48") (pin "1") (pinfunction "1_1") (pintype "passive"))
      (node (ref "C49") (pin "1") (pinfunction "1_1") (pintype "passive"))
      (node (ref "D12") (pin "2") (pinfunction "K_2") (pintype "passive"))
      (node (ref "D13") (pin "1") (pinfunction "A_1") (pintype "passive"))
      (node (ref "D14") (pin "1") (pinfunction "A_1") (pintype "passive"))
      (node (ref "D15") (pin "1") (pinfunction "A_1") (pintype "passive"))
      (node (ref "D16") (pin "1") (pinfunction "A_1") (pintype "passive"))
      (node (ref "R25") (pin "1") (pinfunction "1_1") (pintype "passive"))
      (node (ref "U10") (pin "1") (pinfunction "VCC_1") (pintype "passive"))
      (node (ref "U10") (pin "3") (pinfunction "~{SD}_3") (pintype "passive"))
      (node (ref "U11") (pin "1") (pinfunction "VCC_1") (pintype "passive"))
      (node (ref "U11") (pin "3") (pinfunction "~{SD}_3") (pintype "passive"))
      (node (ref "U12") (pin "1") (pinfunction "VCC_1") (pintype "passive"))
      (node (ref "U12") (pin "3") (pinfunction "~{SD}_3") (pintype "passive"))
      (node (ref "U9") (pin "1") (pinfunction "VCC_1") (pintype "passive"))
      (node (ref "U9") (pin "3") (pinfunction "~{SD}_3") (pintype "passive"))
    )
    (net (code "44") (name "D7V2") (class "Default")
      (node (ref "C1") (pin "1") (pinfunction "1_1") (pintype "passive"))
      (node (ref "C41") (pin "1") (pinfunction "1_1") (pintype "passive"))
      (node (ref "Q2") (pin "2") (pinfunction "D_2") (pintype "passive"))
      (node (ref "Q3") (pin "2") (pinfunction "D_2") (pintype "passive"))
      (node (ref "Q6") (pin "2") (pinfunction "D_2") (pintype "passive"))
      (node (ref "Q7") (pin "2") (pinfunction "D_2") (pintype "passive"))
      (node (ref "R23") (pin "2") (pinfunction "2_2") (pintype "passive"))
      (node (ref "U8") (pin "6") (pinfunction "VCC_6") (pintype "passive"))
      (node (ref "驱动开关1") (pin "2") (pinfunction "2_2") (pintype "passive"))
    )
    (net (code "45") (name "GND") (class "Default")
      (node (ref "C1") (pin "2") (pinfunction "2_2") (pintype "passive"))
      (node (ref "C10") (pin "2") (pinfunction "2_2") (pintype "passive"))
      (node (ref "C11") (pin "2") (pinfunction "2_2") (pintype "passive"))
      (node (ref "C12") (pin "2") (pinfunction "2_2") (pintype "passive"))
      (node (ref "C13") (pin "1") (pinfunction "1_1") (pintype "passive"))
      (node (ref "C14") (pin "2") (pinfunction "2_2") (pintype "passive"))
      (node (ref "C15") (pin "1") (pinfunction "1_1") (pintype "passive"))
      (node (ref "C16") (pin "1") (pinfunction "1_1") (pintype "passive"))
      (node (ref "C19") (pin "2") (pinfunction "2_2") (pintype "passive"))
      (node (ref "C2") (pin "2") (pinfunction "2_2") (pintype "passive"))
      (node (ref "C20") (pin "2") (pinfunction "2_2") (pintype "passive"))
      (node (ref "C21") (pin "1") (pinfunction "1_1") (pintype "passive"))
      (node (ref "C22") (pin "1") (pinfunction "1_1") (pintype "passive"))
      (node (ref "C23") (pin "1") (pinfunction "1_1") (pintype "passive"))
      (node (ref "C24") (pin "1") (pinfunction "1_1") (pintype "passive"))
      (node (ref "C25") (pin "1") (pinfunction "1_1") (pintype "passive"))
      (node (ref "C26") (pin "1") (pinfunction "1_1") (pintype "passive"))
      (node (ref "C3") (pin "2") (pinfunction "2_2") (pintype "passive"))
      (node (ref "C38") (pin "1") (pinfunction "1_1") (pintype "passive"))
      (node (ref "C4") (pin "2") (pinfunction "2_2") (pintype "passive"))
      (node (ref "C5") (pin "2") (pinfunction "2_2") (pintype "passive"))
      (node (ref "C6") (pin "1") (pinfunction "1_1") (pintype "passive"))
      (node (ref "C7") (pin "1") (pinfunction "1_1") (pintype "passive"))
      (node (ref "C8") (pin "1") (pinfunction "1_1") (pintype "passive"))
      (node (ref "C9") (pin "2") (pinfunction "2_2") (pintype "passive"))
      (node (ref "D4") (pin "1") (pinfunction "A_1") (pintype "passive"))
      (node (ref "D5") (pin "1") (pinfunction "A_1") (pintype "passive"))
      (node (ref "IR1") (pin "1") (pinfunction "GND_1") (pintype "passive"))
      (node (ref "J1") (pin "2") (pinfunction "2_2") (pintype "passive"))
      (node (ref "JTAG1") (pin "2") (pinfunction "2_2") (pintype "passive"))
      (node (ref "JTAG1") (pin "3") (pinfunction "3_3") (pintype "passive"))
      (node (ref "P-coder1") (pin "1") (pinfunction "GND_1") (pintype "passive"))
      (node (ref "P-coder2") (pin "1") (pinfunction "GND_1") (pintype "passive"))
      (node (ref "P1") (pin "1") (pinfunction "1_1") (pintype "passive"))
      (node (ref "P1") (pin "2") (pinfunction "2_2") (pintype "passive"))
      (node (ref "P1") (pin "3") (pinfunction "3_3") (pintype "passive"))
      (node (ref "P1") (pin "4") (pinfunction "4_4") (pintype "passive"))
      (node (ref "POWER") (pin "1") (pinfunction "VCC_1") (pintype "passive"))
      (node (ref "Q1") (pin "2") (pinfunction "2_2") (pintype "passive"))
      (node (ref "R10") (pin "2") (pinfunction "2_2") (pintype "passive"))
      (node (ref "R11") (pin "2") (pinfunction "2_2") (pintype "passive"))
      (node (ref "R12") (pin "2") (pinfunction "2_2") (pintype "passive"))
      (node (ref "R14") (pin "2") (pinfunction "2_2") (pintype "passive"))
      (node (ref "R8") (pin "2") (pinfunction "2_2") (pintype "passive"))
      (node (ref "R9") (pin "2") (pinfunction "2_2") (pintype "passive"))
      (node (ref "REED1") (pin "2") (pinfunction "2_2") (pintype "passive"))
      (node (ref "REED1") (pin "4") (pinfunction "4_4") (pintype "passive"))
      (node (ref "RP2") (pin "1") (pinfunction "1_1") (pintype "passive"))
      (node (ref "RP2") (pin "3") (pinfunction "3_3") (pintype "passive"))
      (node (ref "RP2") (pin "5") (pinfunction "5_5") (pintype "passive"))
      (node (ref "RP2") (pin "7") (pinfunction "7_7") (pintype "passive"))
      (node (ref "RST1") (pin "2") (pinfunction "2_2") (pintype "passive"))
      (node (ref "U1") (pin "1") (pinfunction "GND_1") (pintype "passive"))
      (node (ref "U1") (pin "2") (pinfunction "EN_2") (pintype "passive"))
      (node (ref "U2") (pin "1") (pinfunction "GND_1") (pintype "passive"))
      (node (ref "U2") (pin "2") (pinfunction "EN_2") (pintype "passive"))
      (node (ref "U3") (pin "1") (pinfunction "GND_1") (pintype "passive"))
      (node (ref "U3") (pin "2") (pinfunction "EN_2") (pintype "passive"))
      (node (ref "U4") (pin "11") (pinfunction "VREFL_11") (pintype "passive"))
      (node (ref "U4") (pin "12") (pinfunction "VSS/VSSA_12") (pintype "passive"))
      (node (ref "U4") (pin "48") (pinfunction "VSS_48") (pintype "passive"))
      (node (ref "U4") (pin "69") (pinfunction "VSS_69") (pintype "passive"))
      (node (ref "U7") (pin "1") (pinfunction "DIR_1") (pintype "passive"))
      (node (ref "U7") (pin "10") (pinfunction "GND_10") (pintype "passive"))
      (node (ref "U7") (pin "11") (pinfunction "B7_11") (pintype "passive"))
      (node (ref "U7") (pin "12") (pinfunction "B6_12") (pintype "passive"))
      (node (ref "U7") (pin "13") (pinfunction "B5_13") (pintype "passive"))
      (node (ref "U7") (pin "14") (pinfunction "B4_14") (pintype "passive"))
      (node (ref "U7") (pin "19") (pinfunction "~{OE}_19") (pintype "passive"))
      (node (ref "U7") (pin "6") (pinfunction "A4_6") (pintype "passive"))
      (node (ref "U7") (pin "7") (pinfunction "A5_7") (pintype "passive"))
      (node (ref "U7") (pin "8") (pinfunction "A6_8") (pintype "passive"))
      (node (ref "U7") (pin "9") (pinfunction "A7_9") (pintype "passive"))
      (node (ref "Z-blue1") (pin "2") (pinfunction "2_2") (pintype "passive"))
      (node (ref "Z-oled1") (pin "1") (pinfunction "1_1") (pintype "passive"))
    )
    (net (code "46") (name "M7V2") (class "Default")
      (node (ref "C10") (pin "1") (pinfunction "1_1") (pintype "passive"))
      (node (ref "C11") (pin "1") (pinfunction "1_1") (pintype "passive"))
      (node (ref "C12") (pin "1") (pinfunction "1_1") (pintype "passive"))
      (node (ref "C13") (pin "2") (pinfunction "2_2") (pintype "passive"))
      (node (ref "C14") (pin "1") (pinfunction "1_1") (pintype "passive"))
      (node (ref "C2") (pin "1") (pinfunction "1_1") (pintype "passive"))
      (node (ref "C9") (pin "1") (pinfunction "1_1") (pintype "passive"))
      (node (ref "U1") (pin "3") (pinfunction "IN_3") (pintype "passive"))
      (node (ref "U1") (pin "4") (pinfunction "IN_4") (pintype "passive"))
      (node (ref "U2") (pin "3") (pinfunction "IN_3") (pintype "passive"))
      (node (ref "U2") (pin "4") (pinfunction "IN_4") (pintype "passive"))
      (node (ref "U3") (pin "3") (pinfunction "IN_3") (pintype "passive"))
      (node (ref "U3") (pin "4") (pinfunction "IN_4") (pintype "passive"))
      (node (ref "主板开关1") (pin "2") (pinfunction "2_2") (pintype "passive"))
    )
    (net (code "47") (name "Net-(B1-+)") (class "Default")
      (node (ref "B1") (pin "1") (pinfunction "+_1") (pintype "passive"))
      (node (ref "C42") (pin "2") (pinfunction "2_2") (pintype "passive"))
      (node (ref "Q2") (pin "3") (pinfunction "S_3") (pintype "passive"))
      (node (ref "Q4") (pin "2") (pinfunction "D_2") (pintype "passive"))
      (node (ref "U9") (pin "6") (pinfunction "VS_6") (pintype "passive"))
    )
    (net (code "48") (name "Net-(B1--)") (class "Default")
      (node (ref "B1") (pin "2") (pinfunction "-_2") (pintype "passive"))
      (node (ref "C46") (pin "2") (pinfunction "2_2") (pintype "passive"))
      (node (ref "Q6") (pin "3") (pinfunction "S_3") (pintype "passive"))
      (node (ref "Q8") (pin "2") (pinfunction "D_2") (pintype "passive"))
      (node (ref "U11") (pin "6") (pinfunction "VS_6") (pintype "passive"))
    )
    (net (code "49") (name "Net-(B2-+)") (class "Default")
      (node (ref "B2") (pin "1") (pinfunction "+_1") (pintype "passive"))
      (node (ref "C43") (pin "2") (pinfunction "2_2") (pintype "passive"))
      (node (ref "Q3") (pin "3") (pinfunction "S_3") (pintype "passive"))
      (node (ref "Q5") (pin "2") (pinfunction "D_2") (pintype "passive"))
      (node (ref "U10") (pin "6") (pinfunction "VS_6") (pintype "passive"))
    )
    (net (code "50") (name "Net-(B2--)") (class "Default")
      (node (ref "B2") (pin "2") (pinfunction "-_2") (pintype "passive"))
      (node (ref "C47") (pin "2") (pinfunction "2_2") (pintype "passive"))
      (node (ref "Q7") (pin "3") (pinfunction "S_3") (pintype "passive"))
      (node (ref "Q9") (pin "2") (pinfunction "D_2") (pintype "passive"))
      (node (ref "U12") (pin "6") (pinfunction "VS_6") (pintype "passive"))
    )
    (net (code "51") (name "Net-(BZ1-B)") (class "Default")
      (node (ref "BZ1") (pin "2") (pinfunction "B_2") (pintype "passive"))
      (node (ref "Q1") (pin "3") (pinfunction "3_3") (pintype "passive"))
    )
    (net (code "52") (name "Net-(C27-Pad1)") (class "Default")
      (node (ref "C27") (pin "1") (pinfunction "1_1") (pintype "passive"))
      (node (ref "D8") (pin "3") (pintype "bidirectional"))
    )
    (net (code "53") (name "Net-(C31-Pad1)") (class "Default")
      (node (ref "C31") (pin "1") (pinfunction "1_1") (pintype "passive"))
      (node (ref "D9") (pin "3") (pintype "bidirectional"))
    )
    (net (code "54") (name "Net-(C33-Pad1)") (class "Default")
      (node (ref "C33") (pin "1") (pinfunction "1_1") (pintype "passive"))
      (node (ref "D10") (pin "3") (pintype "bidirectional"))
    )
    (net (code "55") (name "Net-(C36-Pad1)") (class "Default")
      (node (ref "C36") (pin "1") (pinfunction "1_1") (pintype "passive"))
      (node (ref "D11") (pin "3") (pintype "bidirectional"))
    )
    (net (code "56") (name "Net-(D3-K)") (class "Default")
      (node (ref "D3") (pin "2") (pinfunction "K_2") (pintype "passive"))
      (node (ref "F1") (pin "1") (pinfunction "1_1") (pintype "passive"))
    )
    (net (code "57") (name "Net-(D6-Pad2)") (class "Default")
      (node (ref "D6") (pin "2") (pinfunction "2_2") (pintype "passive"))
      (node (ref "R8") (pin "1") (pinfunction "1_1") (pintype "passive"))
    )
    (net (code "58") (name "Net-(D7-Pad2)") (class "Default")
      (node (ref "D7") (pin "2") (pinfunction "2_2") (pintype "passive"))
      (node (ref "R15") (pin "1") (pinfunction "1_1") (pintype "passive"))
    )
    (net (code "59") (name "Net-(D12-A)") (class "Default")
      (node (ref "D12") (pin "1") (pinfunction "A_1") (pintype "passive"))
      (node (ref "L2") (pin "2") (pinfunction "2_2") (pintype "passive"))
      (node (ref "U8") (pin "1") (pinfunction "SC_1") (pintype "passive"))
    )
    (net (code "60") (name "Net-(D13-K)") (class "Default")
      (node (ref "C42") (pin "1") (pinfunction "1_1") (pintype "passive"))
      (node (ref "D13") (pin "2") (pinfunction "K_2") (pintype "passive"))
      (node (ref "U9") (pin "8") (pinfunction "VB_8") (pintype "passive"))
    )
    (net (code "61") (name "Net-(D14-K)") (class "Default")
      (node (ref "C43") (pin "1") (pinfunction "1_1") (pintype "passive"))
      (node (ref "D14") (pin "2") (pinfunction "K_2") (pintype "passive"))
      (node (ref "U10") (pin "8") (pinfunction "VB_8") (pintype "passive"))
    )
    (net (code "62") (name "Net-(D15-K)") (class "Default")
      (node (ref "C46") (pin "1") (pinfunction "1_1") (pintype "passive"))
      (node (ref "D15") (pin "2") (pinfunction "K_2") (pintype "passive"))
      (node (ref "U11") (pin "8") (pinfunction "VB_8") (pintype "passive"))
    )
    (net (code "63") (name "Net-(D16-K)") (class "Default")
      (node (ref "C47") (pin "1") (pinfunction "1_1") (pintype "passive"))
      (node (ref "D16") (pin "2") (pinfunction "K_2") (pintype "passive"))
      (node (ref "U12") (pin "8") (pinfunction "VB_8") (pintype "passive"))
    )
    (net (code "64") (name "Net-(Q1-Pad1)") (class "Default")
      (node (ref "Q1") (pin "1") (pinfunction "1_1") (pintype "passive"))
      (node (ref "R6") (pin "1") (pinfunction "1_1") (pintype "passive"))
    )
    (net (code "65") (name "Net-(Q2-G)") (class "Default")
      (node (ref "Q2") (pin "1") (pinfunction "G_1") (pintype "passive"))
      (node (ref "R27") (pin "2") (pinfunction "2_2") (pintype "passive"))
    )
    (net (code "66") (name "Net-(Q3-G)") (class "Default")
      (node (ref "Q3") (pin "1") (pinfunction "G_1") (pintype "passive"))
      (node (ref "R28") (pin "2") (pinfunction "2_2") (pintype "passive"))
    )
    (net (code "67") (name "Net-(Q4-G)") (class "Default")
      (node (ref "Q4") (pin "1") (pinfunction "G_1") (pintype "passive"))
      (node (ref "R29") (pin "2") (pinfunction "2_2") (pintype "passive"))
    )
    (net (code "68") (name "Net-(Q5-G)") (class "Default")
      (node (ref "Q5") (pin "1") (pinfunction "G_1") (pintype "passive"))
      (node (ref "R30") (pin "2") (pinfunction "2_2") (pintype "passive"))
    )
    (net (code "69") (name "Net-(Q6-G)") (class "Default")
      (node (ref "Q6") (pin "1") (pinfunction "G_1") (pintype "passive"))
      (node (ref "R31") (pin "2") (pinfunction "2_2") (pintype "passive"))
    )
    (net (code "70") (name "Net-(Q7-G)") (class "Default")
      (node (ref "Q7") (pin "1") (pinfunction "G_1") (pintype "passive"))
      (node (ref "R32") (pin "2") (pinfunction "2_2") (pintype "passive"))
    )
    (net (code "71") (name "Net-(Q8-G)") (class "Default")
      (node (ref "Q8") (pin "1") (pinfunction "G_1") (pintype "passive"))
      (node (ref "R33") (pin "2") (pinfunction "2_2") (pintype "passive"))
    )
    (net (code "72") (name "Net-(Q9-G)") (class "Default")
      (node (ref "Q9") (pin "1") (pinfunction "G_1") (pintype "passive"))
      (node (ref "R34") (pin "2") (pinfunction "2_2") (pintype "passive"))
    )
    (net (code "73") (name "Net-(U4-VDDA)") (class "Default")
      (node (ref "C20") (pin "1") (pinfunction "1_1") (pintype "passive"))
      (node (ref "C21") (pin "2") (pinfunction "2_2") (pintype "passive"))
      (node (ref "L1") (pin "1") (pinfunction "1_1") (pintype "passive"))
      (node (ref "U4") (pin "10") (pinfunction "VREFH_10") (pintype "passive"))
      (node (ref "U4") (pin "9") (pinfunction "VDDA_9") (pintype "passive"))
    )
    (net (code "74") (name "Net-(U5-IN1+)") (class "Default")
      (node (ref "J2") (pin "1") (pinfunction "1_1") (pintype "passive"))
      (node (ref "U5") (pin "3") (pinfunction "IN1+_3") (pintype "passive"))
    )
    (net (code "75") (name "Net-(U5-IN1-)") (class "Default")
      (node (ref "U5") (pin "2") (pinfunction "IN1-_2") (pintype "passive"))
      (node (ref "VR1") (pin "2") (pinfunction "2_2") (pintype "passive"))
    )
    (net (code "76") (name "Net-(U5-IN2+)") (class "Default")
      (node (ref "J3") (pin "1") (pinfunction "1_1") (pintype "passive"))
      (node (ref "U5") (pin "5") (pinfunction "IN2+_5") (pintype "passive"))
    )
    (net (code "77") (name "Net-(U5-IN2-)") (class "Default")
      (node (ref "U5") (pin "6") (pinfunction "IN2-_6") (pintype "passive"))
      (node (ref "VR2") (pin "2") (pinfunction "2_2") (pintype "passive"))
    )
    (net (code "78") (name "Net-(U5-OUT1)") (class "Default")
      (node (ref "C27") (pin "2") (pinfunction "2_2") (pintype "passive"))
      (node (ref "U5") (pin "1") (pinfunction "OUT1_1") (pintype "passive"))
      (node (ref "VR1") (pin "1") (pinfunction "1_1") (pintype "passive"))
    )
    (net (code "79") (name "Net-(U5-OUT2)") (class "Default")
      (node (ref "C31") (pin "2") (pinfunction "2_2") (pintype "passive"))
      (node (ref "U5") (pin "7") (pinfunction "OUT2_7") (pintype "passive"))
      (node (ref "VR2") (pin "1") (pinfunction "1_1") (pintype "passive"))
    )
    (net (code "80") (name "Net-(U6-IN1+)") (class "Default")
      (node (ref "J4") (pin "1") (pinfunction "1_1") (pintype "passive"))
      (node (ref "U6") (pin "3") (pinfunction "IN1+_3") (pintype "passive"))
    )
    (net (code "81") (name "Net-(U6-IN1-)") (class "Default")
      (node (ref "U6") (pin "2") (pinfunction "IN1-_2") (pintype "passive"))
      (node (ref "VR3") (pin "2") (pinfunction "2_2") (pintype "passive"))
    )
    (net (code "82") (name "Net-(U6-IN2+)") (class "Default")
      (node (ref "J5") (pin "1") (pinfunction "1_1") (pintype "passive"))
      (node (ref "U6") (pin "5") (pinfunction "IN2+_5") (pintype "passive"))
    )
    (net (code "83") (name "Net-(U6-IN2-)") (class "Default")
      (node (ref "U6") (pin "6") (pinfunction "IN2-_6") (pintype "passive"))
      (node (ref "VR4") (pin "2") (pinfunction "2_2") (pintype "passive"))
    )
    (net (code "84") (name "Net-(U6-OUT1)") (class "Default")
      (node (ref "C33") (pin "2") (pinfunction "2_2") (pintype "passive"))
      (node (ref "U6") (pin "1") (pinfunction "OUT1_1") (pintype "passive"))
      (node (ref "VR3") (pin "1") (pinfunction "1_1") (pintype "passive"))
    )
    (net (code "85") (name "Net-(U6-OUT2)") (class "Default")
      (node (ref "C36") (pin "2") (pinfunction "2_2") (pintype "passive"))
      (node (ref "U6") (pin "7") (pinfunction "OUT2_7") (pintype "passive"))
      (node (ref "VR4") (pin "1") (pinfunction "1_1") (pintype "passive"))
    )
    (net (code "86") (name "Net-(U8-DR1)") (class "Default")
      (node (ref "R24") (pin "1") (pinfunction "1_1") (pintype "passive"))
      (node (ref "U8") (pin "8") (pinfunction "DR1_8") (pintype "passive"))
    )
    (net (code "87") (name "Net-(U8-FB)") (class "Default")
      (node (ref "R25") (pin "2") (pinfunction "2_2") (pintype "passive"))
      (node (ref "R26") (pin "2") (pinfunction "2_2") (pintype "passive"))
      (node (ref "U8") (pin "5") (pinfunction "FB_5") (pintype "passive"))
    )
    (net (code "88") (name "Net-(U8-IPK)") (class "Default")
      (node (ref "L2") (pin "1") (pinfunction "1_1") (pintype "passive"))
      (node (ref "R23") (pin "1") (pinfunction "1_1") (pintype "passive"))
      (node (ref "R24") (pin "2") (pinfunction "2_2") (pintype "passive"))
      (node (ref "U8") (pin "7") (pinfunction "IPK_7") (pintype "passive"))
    )
    (net (code "89") (name "Net-(U8-TC)") (class "Default")
      (node (ref "C40") (pin "1") (pinfunction "1_1") (pintype "passive"))
      (node (ref "U8") (pin "3") (pinfunction "TC_3") (pintype "passive"))
    )
    (net (code "90") (name "Net-(U9-HO)") (class "Default")
      (node (ref "R27") (pin "1") (pinfunction "1_1") (pintype "passive"))
      (node (ref "U9") (pin "7") (pinfunction "HO_7") (pintype "passive"))
    )
    (net (code "91") (name "Net-(U9-LO)") (class "Default")
      (node (ref "R29") (pin "1") (pinfunction "1_1") (pintype "passive"))
      (node (ref "U9") (pin "5") (pinfunction "LO_5") (pintype "passive"))
    )
    (net (code "92") (name "Net-(U10-HO)") (class "Default")
      (node (ref "R28") (pin "1") (pinfunction "1_1") (pintype "passive"))
      (node (ref "U10") (pin "7") (pinfunction "HO_7") (pintype "passive"))
    )
    (net (code "93") (name "Net-(U10-LO)") (class "Default")
      (node (ref "R30") (pin "1") (pinfunction "1_1") (pintype "passive"))
      (node (ref "U10") (pin "5") (pinfunction "LO_5") (pintype "passive"))
    )
    (net (code "94") (name "Net-(U11-HO)") (class "Default")
      (node (ref "R31") (pin "1") (pinfunction "1_1") (pintype "passive"))
      (node (ref "U11") (pin "7") (pinfunction "HO_7") (pintype "passive"))
    )
    (net (code "95") (name "Net-(U11-LO)") (class "Default")
      (node (ref "R33") (pin "1") (pinfunction "1_1") (pintype "passive"))
      (node (ref "U11") (pin "5") (pinfunction "LO_5") (pintype "passive"))
    )
    (net (code "96") (name "Net-(U12-HO)") (class "Default")
      (node (ref "R32") (pin "1") (pinfunction "1_1") (pintype "passive"))
      (node (ref "U12") (pin "7") (pinfunction "HO_7") (pintype "passive"))
    )
    (net (code "97") (name "Net-(U12-LO)") (class "Default")
      (node (ref "R34") (pin "1") (pinfunction "1_1") (pintype "passive"))
      (node (ref "U12") (pin "5") (pinfunction "LO_5") (pintype "passive"))
    )
    (net (code "98") (name "PGND") (class "Default")
      (node (ref "C39") (pin "2") (pinfunction "2_2") (pintype "passive"))
      (node (ref "C40") (pin "2") (pinfunction "2_2") (pintype "passive"))
      (node (ref "C41") (pin "2") (pinfunction "2_2") (pintype "passive"))
      (node (ref "C44") (pin "2") (pinfunction "2_2") (pintype "passive"))
      (node (ref "C45") (pin "2") (pinfunction "2_2") (pintype "passive"))
      (node (ref "C48") (pin "2") (pinfunction "2_2") (pintype "passive"))
      (node (ref "C49") (pin "2") (pinfunction "2_2") (pintype "passive"))
      (node (ref "Q4") (pin "3") (pinfunction "S_3") (pintype "passive"))
      (node (ref "Q5") (pin "3") (pinfunction "S_3") (pintype "passive"))
      (node (ref "Q8") (pin "3") (pinfunction "S_3") (pintype "passive"))
      (node (ref "Q9") (pin "3") (pinfunction "S_3") (pintype "passive"))
      (node (ref "R10") (pin "1") (pinfunction "1_1") (pintype "passive"))
      (node (ref "R11") (pin "1") (pinfunction "1_1") (pintype "passive"))
      (node (ref "R12") (pin "1") (pinfunction "1_1") (pintype "passive"))
      (node (ref "R26") (pin "1") (pinfunction "1_1") (pintype "passive"))
      (node (ref "R9") (pin "1") (pinfunction "1_1") (pintype "passive"))
      (node (ref "U10") (pin "4") (pinfunction "COM_4") (pintype "passive"))
      (node (ref "U11") (pin "4") (pinfunction "COM_4") (pintype "passive"))
      (node (ref "U12") (pin "4") (pinfunction "COM_4") (pintype "passive"))
      (node (ref "U8") (pin "2") (pinfunction "SE_2") (pintype "passive"))
      (node (ref "U8") (pin "4") (pinfunction "GND_4") (pintype "passive"))
      (node (ref "U9") (pin "4") (pinfunction "COM_4") (pintype "passive"))
    )
    (net (code "99") (name "RGND") (class "Default")
      (node (ref "C28") (pin "1") (pinfunction "1_1") (pintype "passive"))
      (node (ref "C29") (pin "2") (pinfunction "2_2") (pintype "passive"))
      (node (ref "C30") (pin "1") (pinfunction "1_1") (pintype "passive"))
      (node (ref "C32") (pin "1") (pinfunction "1_1") (pintype "passive"))
      (node (ref "C34") (pin "1") (pinfunction "1_1") (pintype "passive"))
      (node (ref "C35") (pin "1") (pinfunction "1_1") (pintype "passive"))
      (node (ref "C37") (pin "1") (pinfunction "1_1") (pintype "passive"))
      (node (ref "D10") (pin "1") (pintype "bidirectional"))
      (node (ref "D11") (pin "1") (pintype "bidirectional"))
      (node (ref "D8") (pin "1") (pintype "bidirectional"))
      (node (ref "D9") (pin "1") (pintype "bidirectional"))
      (node (ref "R14") (pin "1") (pinfunction "1_1") (pintype "passive"))
      (node (ref "R18") (pin "1") (pinfunction "1_1") (pintype "passive"))
      (node (ref "R19") (pin "1") (pinfunction "1_1") (pintype "passive"))
      (node (ref "R20") (pin "1") (pinfunction "1_1") (pintype "passive"))
      (node (ref "R21") (pin "1") (pinfunction "1_1") (pintype "passive"))
      (node (ref "R22") (pin "1") (pinfunction "1_1") (pintype "passive"))
      (node (ref "U5") (pin "4") (pinfunction "GND_4") (pintype "passive"))
      (node (ref "U6") (pin "4") (pinfunction "GND_4") (pintype "passive"))
    )
    (net (code "100") (name "VDD") (class "Default")
      (node (ref "C22") (pin "2") (pinfunction "2_2") (pintype "passive"))
      (node (ref "C23") (pin "2") (pinfunction "2_2") (pintype "passive"))
      (node (ref "C24") (pin "2") (pinfunction "2_2") (pintype "passive"))
      (node (ref "D4") (pin "2") (pinfunction "K_2") (pintype "passive"))
      (node (ref "D5") (pin "2") (pinfunction "K_2") (pintype "passive"))
      (node (ref "D6") (pin "1") (pinfunction "1_1") (pintype "passive"))
      (node (ref "D7") (pin "1") (pinfunction "1_1") (pintype "passive"))
      (node (ref "F1") (pin "2") (pinfunction "2_2") (pintype "passive"))
      (node (ref "L1") (pin "2") (pinfunction "2_2") (pintype "passive"))
      (node (ref "R7") (pin "1") (pinfunction "1_1") (pintype "passive"))
      (node (ref "U4") (pin "49") (pinfunction "VDD_49") (pintype "passive"))
      (node (ref "U4") (pin "70") (pinfunction "VDD_70") (pintype "passive"))
      (node (ref "U4") (pin "8") (pinfunction "VDD_8") (pintype "passive"))
    )
    (net (code "101") (name "X5V") (class "Default")
      (node (ref "C30") (pin "2") (pinfunction "2_2") (pintype "passive"))
      (node (ref "C35") (pin "2") (pinfunction "2_2") (pintype "passive"))
      (node (ref "C5") (pin "1") (pinfunction "1_1") (pintype "passive"))
      (node (ref "C8") (pin "2") (pinfunction "2_2") (pintype "passive"))
      (node (ref "R17") (pin "2") (pinfunction "2_2") (pintype "passive"))
      (node (ref "U3") (pin "5") (pinfunction "OUT_5") (pintype "passive"))
      (node (ref "U3") (pin "6") (pinfunction "OUT_6") (pintype "passive"))
      (node (ref "U3") (pin "7") (pinfunction "FB_7") (pintype "passive"))
      (node (ref "U5") (pin "8") (pinfunction "VCC_8") (pintype "passive"))
      (node (ref "U6") (pin "8") (pinfunction "VCC_8") (pintype "passive"))
    )
    (net (code "102") (name "unconnected-(JTAG1-Pad4)") (class "Default")
      (node (ref "JTAG1") (pin "4") (pinfunction "4_4") (pintype "passive"))
    )
    (net (code "103") (name "unconnected-(JTAG1-Pad5)") (class "Default")
      (node (ref "JTAG1") (pin "5") (pinfunction "5_5") (pintype "passive"))
    )
    (net (code "104") (name "unconnected-(JTAG1-Pad7)") (class "Default")
      (node (ref "JTAG1") (pin "7") (pinfunction "7_7") (pintype "passive"))
    )
    (net (code "105") (name "unconnected-(JTAG1-Pad8)") (class "Default")
      (node (ref "JTAG1") (pin "8") (pinfunction "8_8") (pintype "passive"))
    )
    (net (code "106") (name "unconnected-(P-coder1-NC-Pad4)") (class "Default")
      (node (ref "P-coder1") (pin "4") (pinfunction "NC_4") (pintype "passive"))
    )
    (net (code "107") (name "unconnected-(P-coder1-Z-Pad3)") (class "Default")
      (node (ref "P-coder1") (pin "3") (pinfunction "Z_3") (pintype "passive"))
    )
    (net (code "108") (name "unconnected-(P-coder2-NC-Pad4)") (class "Default")
      (node (ref "P-coder2") (pin "4") (pinfunction "NC_4") (pintype "passive"))
    )
    (net (code "109") (name "unconnected-(P-coder2-Z-Pad3)") (class "Default")
      (node (ref "P-coder2") (pin "3") (pinfunction "Z_3") (pintype "passive"))
    )
    (net (code "110") (name "unconnected-(U1-REST-Pad8)") (class "Default")
      (node (ref "U1") (pin "8") (pinfunction "REST_8") (pintype "passive"))
    )
    (net (code "111") (name "unconnected-(U2-REST-Pad8)") (class "Default")
      (node (ref "U2") (pin "8") (pinfunction "REST_8") (pintype "passive"))
    )
    (net (code "112") (name "unconnected-(U3-REST-Pad8)") (class "Default")
      (node (ref "U3") (pin "8") (pinfunction "REST_8") (pintype "passive"))
    )
    (net (code "113") (name "unconnected-(U4-PTA2-Pad60)") (class "Default")
      (node (ref "U4") (pin "60") (pinfunction "PTA2_60") (pintype "passive"))
    )
    (net (code "114") (name "unconnected-(U4-PTA3-Pad59)") (class "Default")
      (node (ref "U4") (pin "59") (pinfunction "PTA3_59") (pintype "passive"))
    )
    (net (code "115") (name "unconnected-(U4-PTA6-Pad46)") (class "Default")
      (node (ref "U4") (pin "46") (pinfunction "PTA6_46") (pintype "passive"))
    )
    (net (code "116") (name "unconnected-(U4-PTA7-Pad45)") (class "Default")
      (node (ref "U4") (pin "45") (pinfunction "PTA7_45") (pintype "passive"))
    )
    (net (code "117") (name "unconnected-(U4-PTB0-Pad42)") (class "Default")
      (node (ref "U4") (pin "42") (pinfunction "PTB0_42") (pintype "passive"))
    )
    (net (code "118") (name "unconnected-(U4-PTB1-Pad41)") (class "Default")
      (node (ref "U4") (pin "41") (pinfunction "PTB1_41") (pintype "passive"))
    )
    (net (code "119") (name "unconnected-(U4-PTB3-Pad39)") (class "Default")
      (node (ref "U4") (pin "39") (pinfunction "PTB3_39") (pintype "passive"))
    )
    (net (code "120") (name "unconnected-(U4-PTB4-Pad23)") (class "Default")
      (node (ref "U4") (pin "23") (pinfunction "PTB4_23") (pintype "passive"))
    )
    (net (code "121") (name "unconnected-(U4-PTB5-Pad22)") (class "Default")
      (node (ref "U4") (pin "22") (pinfunction "PTB5_22") (pintype "passive"))
    )
    (net (code "122") (name "unconnected-(U4-PTC0-Pad32)") (class "Default")
      (node (ref "U4") (pin "32") (pinfunction "PTC0_32") (pintype "passive"))
    )
    (net (code "123") (name "unconnected-(U4-PTC1-Pad31)") (class "Default")
      (node (ref "U4") (pin "31") (pinfunction "PTC1_31") (pintype "passive"))
    )
    (net (code "124") (name "unconnected-(U4-PTC2-Pad25)") (class "Default")
      (node (ref "U4") (pin "25") (pinfunction "PTC2_25") (pintype "passive"))
    )
    (net (code "125") (name "unconnected-(U4-PTC3-Pad24)") (class "Default")
      (node (ref "U4") (pin "24") (pinfunction "PTC3_24") (pintype "passive"))
    )
    (net (code "126") (name "unconnected-(U4-PTC5-Pad77)") (class "Default")
      (node (ref "U4") (pin "77") (pinfunction "PTC5_77") (pintype "passive"))
    )
    (net (code "127") (name "unconnected-(U4-PTD2-Pad58)") (class "Default")
      (node (ref "U4") (pin "58") (pinfunction "PTD2_58") (pintype "passive"))
    )
    (net (code "128") (name "unconnected-(U4-PTD3-Pad57)") (class "Default")
      (node (ref "U4") (pin "57") (pinfunction "PTD3_57") (pintype "passive"))
    )
    (net (code "129") (name "unconnected-(U4-PTD4-Pad56)") (class "Default")
      (node (ref "U4") (pin "56") (pinfunction "PTD4_56") (pintype "passive"))
    )
    (net (code "130") (name "unconnected-(U4-PTD5-Pad28)") (class "Default")
      (node (ref "U4") (pin "28") (pinfunction "PTD5_28") (pintype "passive"))
    )
    (net (code "131") (name "unconnected-(U4-PTD6-Pad27)") (class "Default")
      (node (ref "U4") (pin "27") (pinfunction "PTD6_27") (pintype "passive"))
    )
    (net (code "132") (name "unconnected-(U4-PTD7-Pad26)") (class "Default")
      (node (ref "U4") (pin "26") (pinfunction "PTD7_26") (pintype "passive"))
    )
    (net (code "133") (name "unconnected-(U4-PTE4-Pad47)") (class "Default")
      (node (ref "U4") (pin "47") (pinfunction "PTE4_47") (pintype "passive"))
    )
    (net (code "134") (name "unconnected-(U4-PTE5-Pad21)") (class "Default")
      (node (ref "U4") (pin "21") (pinfunction "PTE5_21") (pintype "passive"))
    )
    (net (code "135") (name "unconnected-(U4-PTE6-Pad20)") (class "Default")
      (node (ref "U4") (pin "20") (pinfunction "PTE6_20") (pintype "passive"))
    )
    (net (code "136") (name "unconnected-(U4-PTF0-Pad55)") (class "Default")
      (node (ref "U4") (pin "55") (pinfunction "PTF0_55") (pintype "passive"))
    )
    (net (code "137") (name "unconnected-(U4-PTF1-Pad54)") (class "Default")
      (node (ref "U4") (pin "54") (pinfunction "PTF1_54") (pintype "passive"))
    )
    (net (code "138") (name "unconnected-(U4-PTF2-Pad44)") (class "Default")
      (node (ref "U4") (pin "44") (pinfunction "PTF2_44") (pintype "passive"))
    )
    (net (code "139") (name "unconnected-(U4-PTF3-Pad43)") (class "Default")
      (node (ref "U4") (pin "43") (pinfunction "PTF3_43") (pintype "passive"))
    )
    (net (code "140") (name "unconnected-(U4-PTH0-Pad19)") (class "Default")
      (node (ref "U4") (pin "19") (pinfunction "PTH0_19") (pintype "passive"))
    )
    (net (code "141") (name "unconnected-(U4-PTH1-Pad18)") (class "Default")
      (node (ref "U4") (pin "18") (pinfunction "PTH1_18") (pintype "passive"))
    )
    (net (code "142") (name "unconnected-(U4-PTH2-Pad7)") (class "Default")
      (node (ref "U4") (pin "7") (pinfunction "PTH2_7") (pintype "passive"))
    )
    (net (code "143") (name "unconnected-(U4-PTH3-Pad34)") (class "Default")
      (node (ref "U4") (pin "34") (pinfunction "PTH3_34") (pintype "passive"))
    )
    (net (code "144") (name "unconnected-(U4-PTH4-Pad33)") (class "Default")
      (node (ref "U4") (pin "33") (pinfunction "PTH4_33") (pintype "passive"))
    )
    (net (code "145") (name "unconnected-(U4-PTI0-Pad17)") (class "Default")
      (node (ref "U4") (pin "17") (pinfunction "PTI0_17") (pintype "passive"))
    )
    (net (code "146") (name "unconnected-(U4-PTI2-Pad66)") (class "Default")
      (node (ref "U4") (pin "66") (pinfunction "PTI2_66") (pintype "passive"))
    )
    (net (code "147") (name "unconnected-(U4-PTI5-Pad30)") (class "Default")
      (node (ref "U4") (pin "30") (pinfunction "PTI5_30") (pintype "passive"))
    )
    (net (code "148") (name "unconnected-(U4-PTI6-Pad29)") (class "Default")
      (node (ref "U4") (pin "29") (pinfunction "PTI6_29") (pintype "passive"))
    )
    (net (code "149") (name "unconnected-(Y1-GND-Pad2)") (class "Default")
      (node (ref "Y1") (pin "2") (pinfunction "GND_2") (pintype "passive"))
    )
    (net (code "150") (name "unconnected-(Y1-VDD-Pad4)") (class "Default")
      (node (ref "Y1") (pin "4") (pinfunction "VDD_4") (pintype "passive"))
    )
  )
)
